# hand_main_v2.net
KiCad netlist of a schematic drawn in Altium Designer
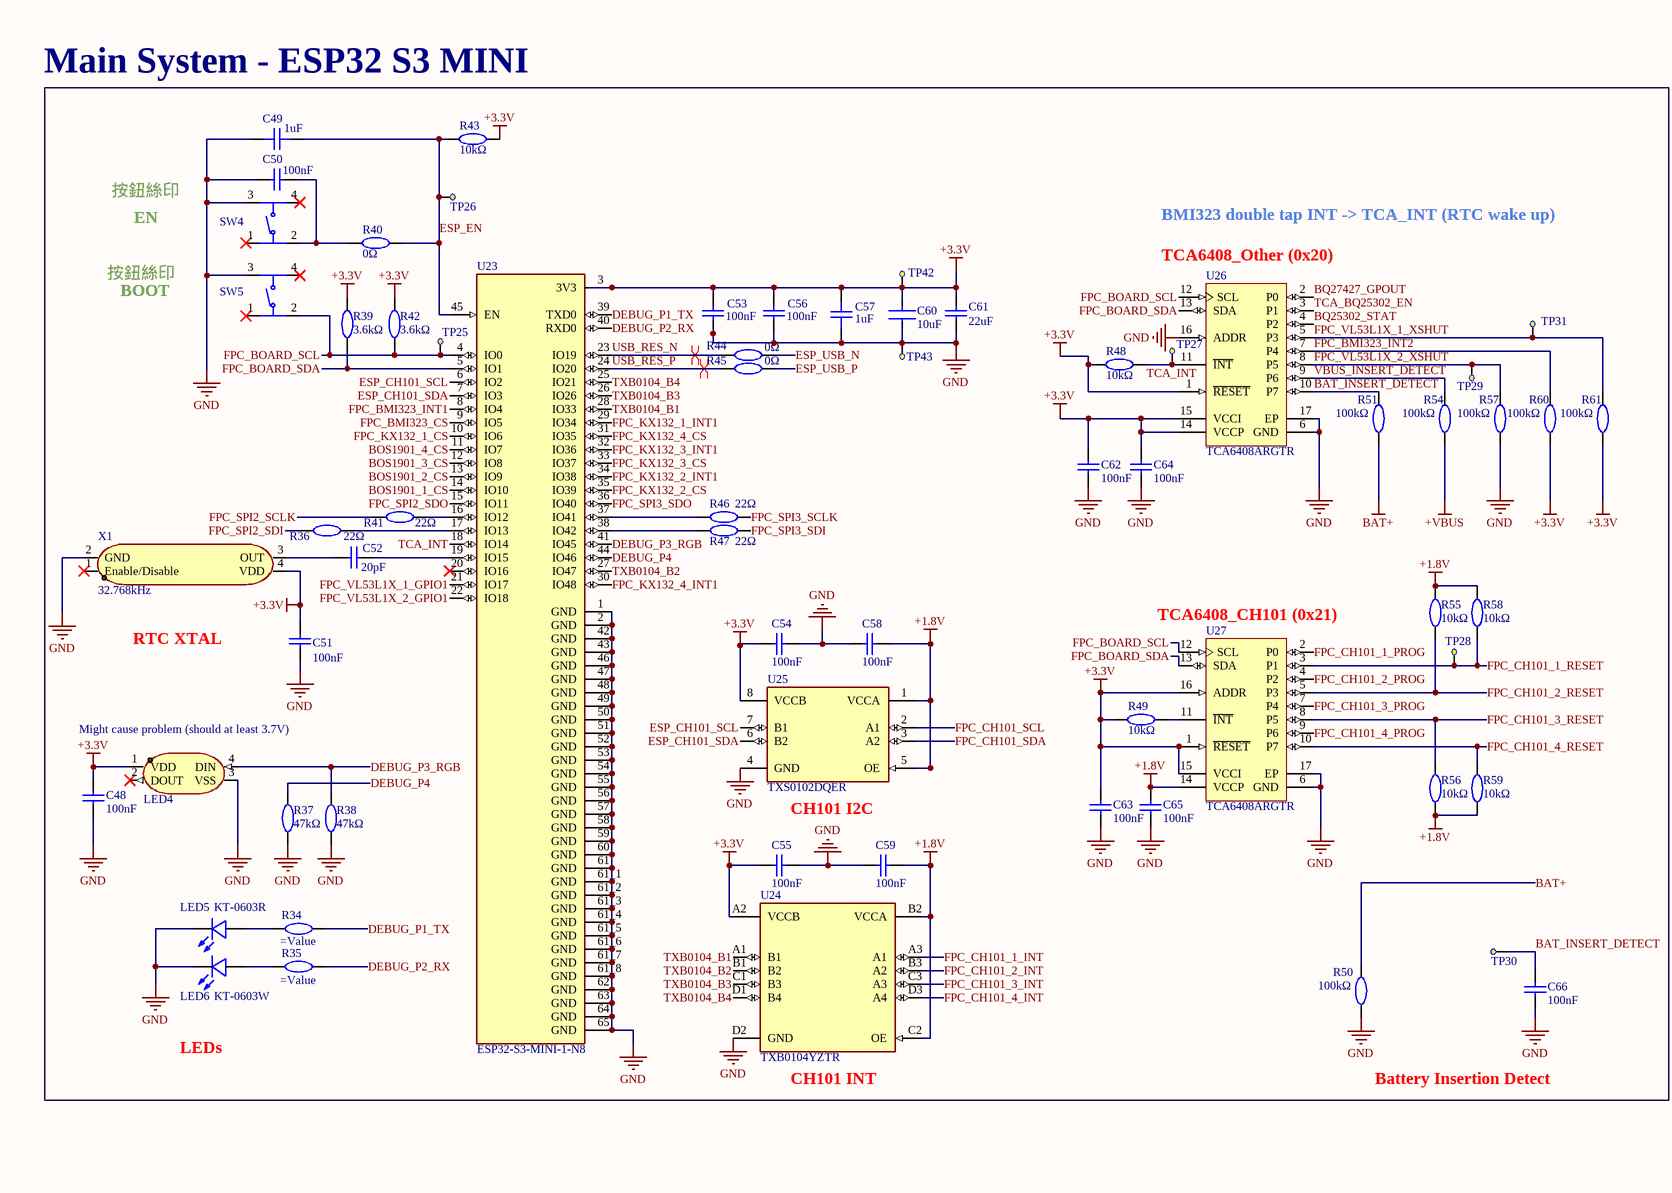
[diagram p0: hand_main_v2.SchDoc, left]
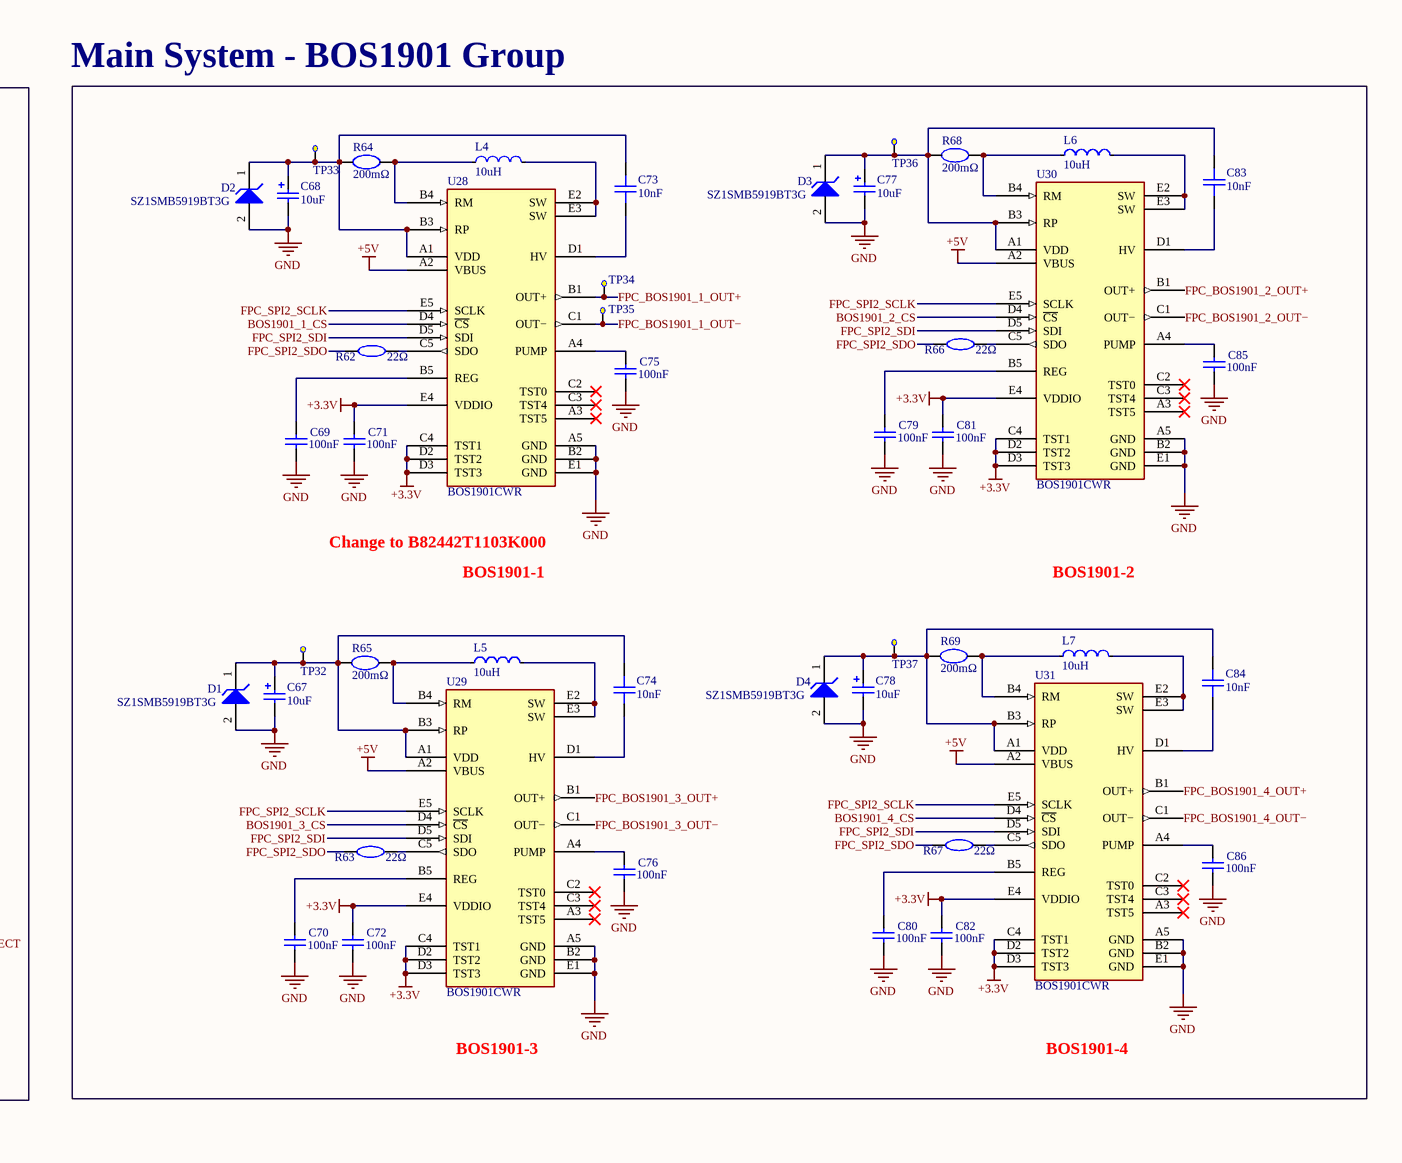
[diagram p1: hand_main_v2.SchDoc, middle]
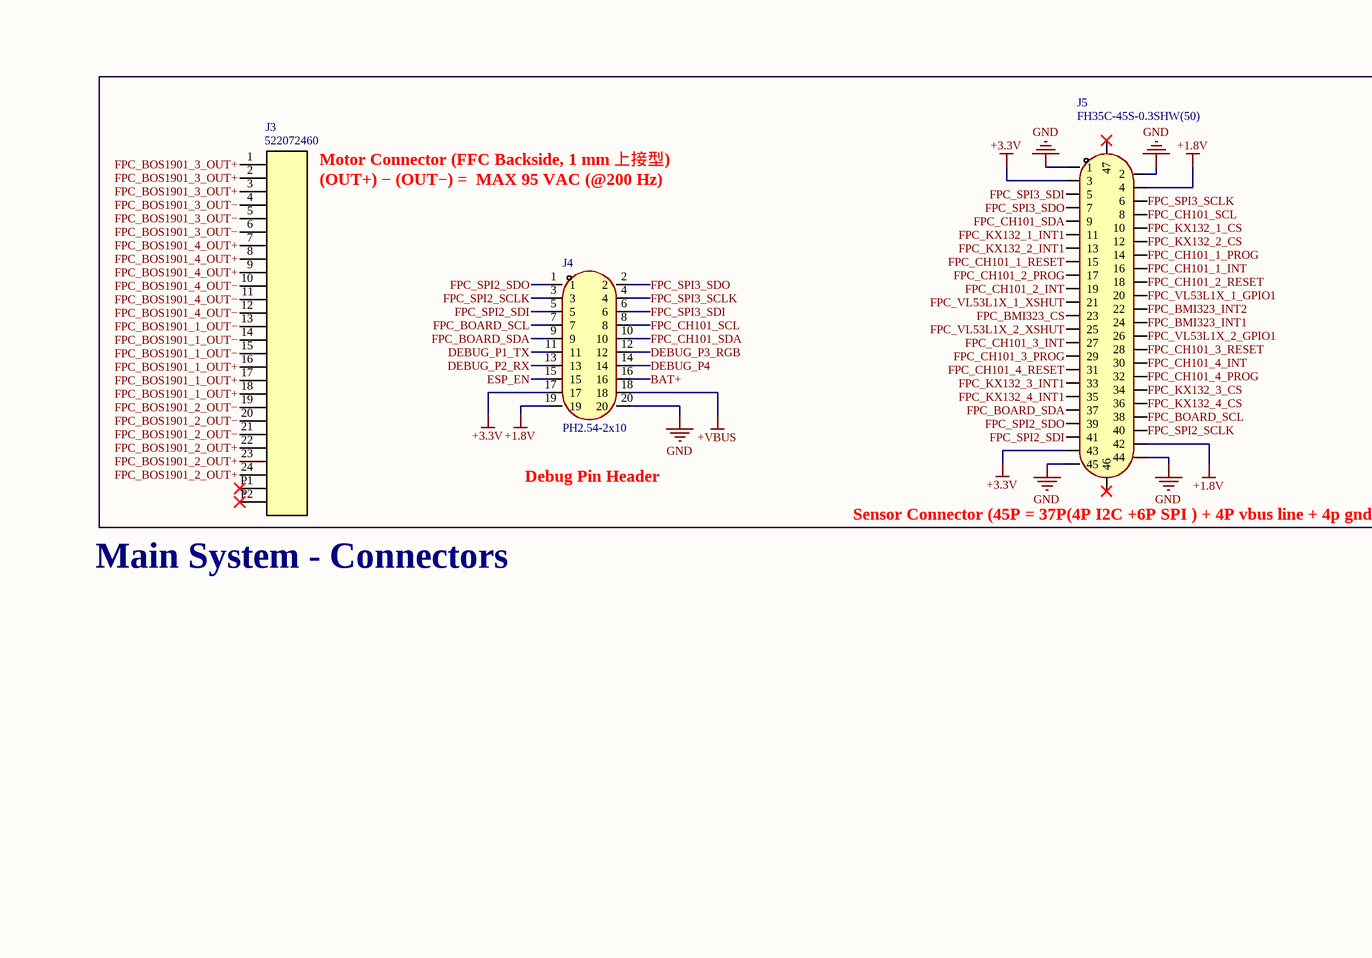
[diagram p2: hand_main_v2.SchDoc, right]

(export (version "E")
  (design (tool "Eeschema 10.0.6"))
  (components
    (comp (ref "C48")
      (value "100nF")
      (footprint "CAPC1050X55X23NL05T13")
      (description "Chip Capacitor, 100 nF, +/- 10%, 16 V, -55 to 125 degC, 0402 (1005 Metric), RoHS, Tape and Reel")
      (fields (field (name "MANUFACTURER") "Samsung Electro-Mechanics"))
      (libsource (lib "hand_ad_lib") (part "CL05B104KO5NNNC"))
    )
    (comp (ref "C49")
      (value "1uF")
      (footprint "C0402")
      (description "MLCC, 1 uF, 25 V, ± 10%, X5R, 0402 [1005 Metric]")
      (fields
        (field (name "MANUFACTURER") "SAMSUNG(三星)")
        (field (name "MANUFACTURER PART") "CL05A105KA5NQNC")
        (field (name "NAME") "1uF")
      )
      (libsource (lib "hand_ad_lib") (part "CL05A105KA5NQNC"))
    )
    (comp (ref "C50")
      (value "100nF")
      (footprint "CAPC1050X55X23NL05T13")
      (description "Chip Capacitor, 100 nF, +/- 10%, 16 V, -55 to 125 degC, 0402 (1005 Metric), RoHS, Tape and Reel")
      (fields (field (name "MANUFACTURER") "Samsung Electro-Mechanics"))
      (libsource (lib "hand_ad_lib") (part "CL05B104KO5NNNC"))
    )
    (comp (ref "C51")
      (value "100nF")
      (footprint "CAPC1050X55X23NL05T13")
      (description "Chip Capacitor, 100 nF, +/- 10%, 16 V, -55 to 125 degC, 0402 (1005 Metric), RoHS, Tape and Reel")
      (fields (field (name "MANUFACTURER") "Samsung Electro-Mechanics"))
      (libsource (lib "hand_ad_lib") (part "CL05B104KO5NNNC"))
    )
    (comp (ref "C52")
      (value "20pF")
      (footprint "C0603")
      (description "MLCC, 20pF, 50 V, ± 5%, C0G, 0603 [1608 Metric]")
      (fields
        (field (name "MANUFACTURER") "SAMSUNG(三星)")
        (field (name "MANUFACTURER PART") "CL10C200JB8NNNC")
        (field (name "NAME") "20pF")
      )
      (libsource (lib "hand_ad_lib") (part "CL10C200JB8NNNC"))
    )
    (comp (ref "C53")
      (value "100nF")
      (footprint "CAPC1050X55X23NL05T13")
      (description "Chip Capacitor, 100 nF, +/- 10%, 16 V, -55 to 125 degC, 0402 (1005 Metric), RoHS, Tape and Reel")
      (fields (field (name "MANUFACTURER") "Samsung Electro-Mechanics"))
      (libsource (lib "hand_ad_lib") (part "CL05B104KO5NNNC"))
    )
    (comp (ref "C54")
      (value "100nF")
      (footprint "CAPC1050X55X23NL05T13")
      (description "Chip Capacitor, 100 nF, +/- 10%, 16 V, -55 to 125 degC, 0402 (1005 Metric), RoHS, Tape and Reel")
      (fields (field (name "MANUFACTURER") "Samsung Electro-Mechanics"))
      (libsource (lib "hand_ad_lib") (part "CL05B104KO5NNNC"))
    )
    (comp (ref "C55")
      (value "100nF")
      (footprint "CAPC1050X55X23NL05T13")
      (description "Chip Capacitor, 100 nF, +/- 10%, 16 V, -55 to 125 degC, 0402 (1005 Metric), RoHS, Tape and Reel")
      (fields (field (name "MANUFACTURER") "Samsung Electro-Mechanics"))
      (libsource (lib "hand_ad_lib") (part "CL05B104KO5NNNC"))
    )
    (comp (ref "C56")
      (value "100nF")
      (footprint "CAPC1050X55X23NL05T13")
      (description "Chip Capacitor, 100 nF, +/- 10%, 16 V, -55 to 125 degC, 0402 (1005 Metric), RoHS, Tape and Reel")
      (fields (field (name "MANUFACTURER") "Samsung Electro-Mechanics"))
      (libsource (lib "hand_ad_lib") (part "CL05B104KO5NNNC"))
    )
    (comp (ref "C57")
      (value "1uF")
      (footprint "C0402")
      (description "MLCC, 1 uF, 25 V, ± 10%, X5R, 0402 [1005 Metric]")
      (fields
        (field (name "MANUFACTURER") "SAMSUNG(三星)")
        (field (name "MANUFACTURER PART") "CL05A105KA5NQNC")
        (field (name "NAME") "1uF")
      )
      (libsource (lib "hand_ad_lib") (part "CL05A105KA5NQNC"))
    )
    (comp (ref "C58")
      (value "100nF")
      (footprint "CAPC1050X55X23NL05T13")
      (description "Chip Capacitor, 100 nF, +/- 10%, 16 V, -55 to 125 degC, 0402 (1005 Metric), RoHS, Tape and Reel")
      (fields (field (name "MANUFACTURER") "Samsung Electro-Mechanics"))
      (libsource (lib "hand_ad_lib") (part "CL05B104KO5NNNC"))
    )
    (comp (ref "C59")
      (value "100nF")
      (footprint "CAPC1050X55X23NL05T13")
      (description "Chip Capacitor, 100 nF, +/- 10%, 16 V, -55 to 125 degC, 0402 (1005 Metric), RoHS, Tape and Reel")
      (fields (field (name "MANUFACTURER") "Samsung Electro-Mechanics"))
      (libsource (lib "hand_ad_lib") (part "CL05B104KO5NNNC"))
    )
    (comp (ref "C60")
      (value "10uF")
      (footprint "FP-CL10-IPC_A")
      (description "Cap Ceramic 10uF 25V X5R ±20% Pad SMD 0603 +85°C T/R")
      (fields (field (name "TOLERANCE") "20%"))
      (libsource (lib "hand_ad_lib") (part "CL10A106MA8NRNC"))
    )
    (comp (ref "C61")
      (value "22uF")
      (footprint "CAPC2013X140X45ML15T25")
      (description "Multi-layer Ceramic Capacitor, 22 uF, -55 to 85 degC, 2-Pin SMD (0805), RoHS, Tape and Reel")
      (fields (field (name "MANUFACTURER") "Samsung Electro-Mechanics") (field (name "TOLERANCE") "±20%"))
      (libsource (lib "hand_ad_lib") (part "CL21A226MAQNNNE"))
    )
    (comp (ref "C62")
      (value "100nF")
      (footprint "CAPC1050X55X23NL05T13")
      (description "Chip Capacitor, 100 nF, +/- 10%, 16 V, -55 to 125 degC, 0402 (1005 Metric), RoHS, Tape and Reel")
      (fields (field (name "MANUFACTURER") "Samsung Electro-Mechanics"))
      (libsource (lib "hand_ad_lib") (part "CL05B104KO5NNNC"))
    )
    (comp (ref "C63")
      (value "100nF")
      (footprint "CAPC1050X55X23NL05T13")
      (description "Chip Capacitor, 100 nF, +/- 10%, 16 V, -55 to 125 degC, 0402 (1005 Metric), RoHS, Tape and Reel")
      (fields (field (name "MANUFACTURER") "Samsung Electro-Mechanics"))
      (libsource (lib "hand_ad_lib") (part "CL05B104KO5NNNC"))
    )
    (comp (ref "C64")
      (value "100nF")
      (footprint "CAPC1050X55X23NL05T13")
      (description "Chip Capacitor, 100 nF, +/- 10%, 16 V, -55 to 125 degC, 0402 (1005 Metric), RoHS, Tape and Reel")
      (fields (field (name "MANUFACTURER") "Samsung Electro-Mechanics"))
      (libsource (lib "hand_ad_lib") (part "CL05B104KO5NNNC"))
    )
    (comp (ref "C65")
      (value "100nF")
      (footprint "CAPC1050X55X23NL05T13")
      (description "Chip Capacitor, 100 nF, +/- 10%, 16 V, -55 to 125 degC, 0402 (1005 Metric), RoHS, Tape and Reel")
      (fields (field (name "MANUFACTURER") "Samsung Electro-Mechanics"))
      (libsource (lib "hand_ad_lib") (part "CL05B104KO5NNNC"))
    )
    (comp (ref "C66")
      (value "100nF")
      (footprint "CAPC1050X55X23NL05T13")
      (description "Chip Capacitor, 100 nF, +/- 10%, 16 V, -55 to 125 degC, 0402 (1005 Metric), RoHS, Tape and Reel")
      (fields (field (name "MANUFACTURER") "Samsung Electro-Mechanics"))
      (libsource (lib "hand_ad_lib") (part "CL05B104KO5NNNC"))
    )
    (comp (ref "C67")
      (value "10uF")
      (footprint "CAP-SMD_L3.2-W1.6-RD-C7171")
      (fields
        (field (name "MANUFACTURER") "Kyocera AVX")
        (field (name "MANUFACTURER PART") "TAJA106K016RNJ")
        (field (name "TOLERANCE") "±10%")
        (field (name "NAME") "10uF")
      )
      (libsource (lib "hand_ad_lib") (part "TAJA106K016RNJ"))
    )
    (comp (ref "C68")
      (value "10uF")
      (footprint "CAP-SMD_L3.2-W1.6-RD-C7171")
      (fields
        (field (name "MANUFACTURER") "Kyocera AVX")
        (field (name "MANUFACTURER PART") "TAJA106K016RNJ")
        (field (name "TOLERANCE") "±10%")
        (field (name "NAME") "10uF")
      )
      (libsource (lib "hand_ad_lib") (part "TAJA106K016RNJ"))
    )
    (comp (ref "C69")
      (value "100nF")
      (footprint "CAPC1050X55X23NL05T13")
      (description "Chip Capacitor, 100 nF, +/- 10%, 16 V, -55 to 125 degC, 0402 (1005 Metric), RoHS, Tape and Reel")
      (fields (field (name "MANUFACTURER") "Samsung Electro-Mechanics"))
      (libsource (lib "hand_ad_lib") (part "CL05B104KO5NNNC"))
    )
    (comp (ref "C70")
      (value "100nF")
      (footprint "CAPC1050X55X23NL05T13")
      (description "Chip Capacitor, 100 nF, +/- 10%, 16 V, -55 to 125 degC, 0402 (1005 Metric), RoHS, Tape and Reel")
      (fields (field (name "MANUFACTURER") "Samsung Electro-Mechanics"))
      (libsource (lib "hand_ad_lib") (part "CL05B104KO5NNNC"))
    )
    (comp (ref "C71")
      (value "100nF")
      (footprint "CAPC1050X55X23NL05T13")
      (description "Chip Capacitor, 100 nF, +/- 10%, 16 V, -55 to 125 degC, 0402 (1005 Metric), RoHS, Tape and Reel")
      (fields (field (name "MANUFACTURER") "Samsung Electro-Mechanics"))
      (libsource (lib "hand_ad_lib") (part "CL05B104KO5NNNC"))
    )
    (comp (ref "C72")
      (value "100nF")
      (footprint "CAPC1050X55X23NL05T13")
      (description "Chip Capacitor, 100 nF, +/- 10%, 16 V, -55 to 125 degC, 0402 (1005 Metric), RoHS, Tape and Reel")
      (fields (field (name "MANUFACTURER") "Samsung Electro-Mechanics"))
      (libsource (lib "hand_ad_lib") (part "CL05B104KO5NNNC"))
    )
    (comp (ref "C73")
      (value "10nF")
      (footprint "C1206")
      (description "Cap Ceramic 0.01uF 250V C0G 5% SMD 1206 125°C Embossed T/R")
      (fields
        (field (name "MANUFACTURER") "muRata(村田)")
        (field (name "MANUFACTURER PART") "GCM31B5C2E103JX01L")
        (field (name "NAME") "10nF")
      )
      (libsource (lib "hand_ad_lib") (part "GCM31B5C2E103JX01L"))
    )
    (comp (ref "C74")
      (value "10nF")
      (footprint "C1206")
      (description "Cap Ceramic 0.01uF 250V C0G 5% SMD 1206 125°C Embossed T/R")
      (fields
        (field (name "MANUFACTURER") "muRata(村田)")
        (field (name "MANUFACTURER PART") "GCM31B5C2E103JX01L")
        (field (name "NAME") "10nF")
      )
      (libsource (lib "hand_ad_lib") (part "GCM31B5C2E103JX01L"))
    )
    (comp (ref "C75")
      (value "100nF")
      (footprint "CAPC1050X55X23NL05T13")
      (description "Chip Capacitor, 100 nF, +/- 10%, 16 V, -55 to 125 degC, 0402 (1005 Metric), RoHS, Tape and Reel")
      (fields (field (name "MANUFACTURER") "Samsung Electro-Mechanics"))
      (libsource (lib "hand_ad_lib") (part "CL05B104KO5NNNC"))
    )
    (comp (ref "C76")
      (value "100nF")
      (footprint "CAPC1050X55X23NL05T13")
      (description "Chip Capacitor, 100 nF, +/- 10%, 16 V, -55 to 125 degC, 0402 (1005 Metric), RoHS, Tape and Reel")
      (fields (field (name "MANUFACTURER") "Samsung Electro-Mechanics"))
      (libsource (lib "hand_ad_lib") (part "CL05B104KO5NNNC"))
    )
    (comp (ref "C77")
      (value "10uF")
      (footprint "CAP-SMD_L3.2-W1.6-RD-C7171")
      (fields
        (field (name "MANUFACTURER") "Kyocera AVX")
        (field (name "MANUFACTURER PART") "TAJA106K016RNJ")
        (field (name "TOLERANCE") "±10%")
        (field (name "NAME") "10uF")
      )
      (libsource (lib "hand_ad_lib") (part "TAJA106K016RNJ"))
    )
    (comp (ref "C78")
      (value "10uF")
      (footprint "CAP-SMD_L3.2-W1.6-RD-C7171")
      (fields
        (field (name "MANUFACTURER") "Kyocera AVX")
        (field (name "MANUFACTURER PART") "TAJA106K016RNJ")
        (field (name "TOLERANCE") "±10%")
        (field (name "NAME") "10uF")
      )
      (libsource (lib "hand_ad_lib") (part "TAJA106K016RNJ"))
    )
    (comp (ref "C79")
      (value "100nF")
      (footprint "CAPC1050X55X23NL05T13")
      (description "Chip Capacitor, 100 nF, +/- 10%, 16 V, -55 to 125 degC, 0402 (1005 Metric), RoHS, Tape and Reel")
      (fields (field (name "MANUFACTURER") "Samsung Electro-Mechanics"))
      (libsource (lib "hand_ad_lib") (part "CL05B104KO5NNNC"))
    )
    (comp (ref "C80")
      (value "100nF")
      (footprint "CAPC1050X55X23NL05T13")
      (description "Chip Capacitor, 100 nF, +/- 10%, 16 V, -55 to 125 degC, 0402 (1005 Metric), RoHS, Tape and Reel")
      (fields (field (name "MANUFACTURER") "Samsung Electro-Mechanics"))
      (libsource (lib "hand_ad_lib") (part "CL05B104KO5NNNC"))
    )
    (comp (ref "C81")
      (value "100nF")
      (footprint "CAPC1050X55X23NL05T13")
      (description "Chip Capacitor, 100 nF, +/- 10%, 16 V, -55 to 125 degC, 0402 (1005 Metric), RoHS, Tape and Reel")
      (fields (field (name "MANUFACTURER") "Samsung Electro-Mechanics"))
      (libsource (lib "hand_ad_lib") (part "CL05B104KO5NNNC"))
    )
    (comp (ref "C82")
      (value "100nF")
      (footprint "CAPC1050X55X23NL05T13")
      (description "Chip Capacitor, 100 nF, +/- 10%, 16 V, -55 to 125 degC, 0402 (1005 Metric), RoHS, Tape and Reel")
      (fields (field (name "MANUFACTURER") "Samsung Electro-Mechanics"))
      (libsource (lib "hand_ad_lib") (part "CL05B104KO5NNNC"))
    )
    (comp (ref "C83")
      (value "10nF")
      (footprint "C1206")
      (description "Cap Ceramic 0.01uF 250V C0G 5% SMD 1206 125°C Embossed T/R")
      (fields
        (field (name "MANUFACTURER") "muRata(村田)")
        (field (name "MANUFACTURER PART") "GCM31B5C2E103JX01L")
        (field (name "NAME") "10nF")
      )
      (libsource (lib "hand_ad_lib") (part "GCM31B5C2E103JX01L"))
    )
    (comp (ref "C84")
      (value "10nF")
      (footprint "C1206")
      (description "Cap Ceramic 0.01uF 250V C0G 5% SMD 1206 125°C Embossed T/R")
      (fields
        (field (name "MANUFACTURER") "muRata(村田)")
        (field (name "MANUFACTURER PART") "GCM31B5C2E103JX01L")
        (field (name "NAME") "10nF")
      )
      (libsource (lib "hand_ad_lib") (part "GCM31B5C2E103JX01L"))
    )
    (comp (ref "C85")
      (value "100nF")
      (footprint "CAPC1050X55X23NL05T13")
      (description "Chip Capacitor, 100 nF, +/- 10%, 16 V, -55 to 125 degC, 0402 (1005 Metric), RoHS, Tape and Reel")
      (fields (field (name "MANUFACTURER") "Samsung Electro-Mechanics"))
      (libsource (lib "hand_ad_lib") (part "CL05B104KO5NNNC"))
    )
    (comp (ref "C86")
      (value "100nF")
      (footprint "CAPC1050X55X23NL05T13")
      (description "Chip Capacitor, 100 nF, +/- 10%, 16 V, -55 to 125 degC, 0402 (1005 Metric), RoHS, Tape and Reel")
      (fields (field (name "MANUFACTURER") "Samsung Electro-Mechanics"))
      (libsource (lib "hand_ad_lib") (part "CL05B104KO5NNNC"))
    )
    (comp (ref "D1")
      (value "SZ1SMB5919BT3G")
      (footprint "ONSC-SMB-2-403A-03_H_V")
      (description "3 W Zener Voltage Regulator, 2-Pin SMB, Pb-Free, Tape and Reel")
      (fields (field (name "MANUFACTURER") "On Semiconductor"))
      (libsource (lib "hand_ad_lib") (part "SZ1SMB5919BT3G"))
    )
    (comp (ref "D2")
      (value "SZ1SMB5919BT3G")
      (footprint "ONSC-SMB-2-403A-03_H_V")
      (description "3 W Zener Voltage Regulator, 2-Pin SMB, Pb-Free, Tape and Reel")
      (fields (field (name "MANUFACTURER") "On Semiconductor"))
      (libsource (lib "hand_ad_lib") (part "SZ1SMB5919BT3G"))
    )
    (comp (ref "D3")
      (value "SZ1SMB5919BT3G")
      (footprint "ONSC-SMB-2-403A-03_H_V")
      (description "3 W Zener Voltage Regulator, 2-Pin SMB, Pb-Free, Tape and Reel")
      (fields (field (name "MANUFACTURER") "On Semiconductor"))
      (libsource (lib "hand_ad_lib") (part "SZ1SMB5919BT3G"))
    )
    (comp (ref "D4")
      (value "SZ1SMB5919BT3G")
      (footprint "ONSC-SMB-2-403A-03_H_V")
      (description "3 W Zener Voltage Regulator, 2-Pin SMB, Pb-Free, Tape and Reel")
      (fields (field (name "MANUFACTURER") "On Semiconductor"))
      (libsource (lib "hand_ad_lib") (part "SZ1SMB5919BT3G"))
    )
    (comp (ref "J3")
      (value "522072460")
      (footprint "CON_522072460_MOL")
      (description "FFC 1mm 24P")
      (libsource (lib "hand_ad_lib") (part "522072460"))
    )
    (comp (ref "J4")
      (value "PH2.54-2x10")
      (footprint "HDR-TH_20P-P2.54-V-M-R2-C10-S2.54")
      (description "Pin Header 2.54mm, 2x10")
      (fields (field (name "MANUFACTURER") "ZHOURI(洲日)") (field (name "NAME") "PH2.54-2x10"))
      (libsource (lib "hand_ad_lib") (part "PH2.54-2x10"))
    )
    (comp (ref "J5")
      (value "FH35C-45S-0.3SHW(50)")
      (footprint "FPC-SMD_FH35C-45S-0.3SHW-50")
      (description "FPC Connector, 45P, 0.3mm, Right Angle, Double Side Connection")
      (fields (field (name "MANUFACTURER") "HRS(广濑)") (field (name "NAME") "FH35C-45S-0.3SHW(50)"))
      (libsource (lib "hand_ad_lib") (part "FH35C-45S-0.3SHW(50)"))
    )
    (comp (ref "L4")
      (value "10uH")
      (footprint "IND-SMD_L7.8-W7.0-A")
      (description "Ind Power Unshielded Wirewound 10uH 10% 2.52MHz 2.3A Carrier T/R")
      (fields
        (field (name "MANUFACTURER") "Sumida(胜美达)")
        (field (name "MANUFACTURER PART") "CD75T125NP-100KC")
        (field (name "NAME") "10uH")
      )
      (libsource (lib "hand_ad_lib") (part "CD75T125NP-100KC"))
    )
    (comp (ref "L5")
      (value "10uH")
      (footprint "IND-SMD_L7.8-W7.0-A")
      (description "Ind Power Unshielded Wirewound 10uH 10% 2.52MHz 2.3A Carrier T/R")
      (fields
        (field (name "MANUFACTURER") "Sumida(胜美达)")
        (field (name "MANUFACTURER PART") "CD75T125NP-100KC")
        (field (name "NAME") "10uH")
      )
      (libsource (lib "hand_ad_lib") (part "CD75T125NP-100KC"))
    )
    (comp (ref "L6")
      (value "10uH")
      (footprint "IND-SMD_L7.8-W7.0-A")
      (description "Ind Power Unshielded Wirewound 10uH 10% 2.52MHz 2.3A Carrier T/R")
      (fields
        (field (name "MANUFACTURER") "Sumida(胜美达)")
        (field (name "MANUFACTURER PART") "CD75T125NP-100KC")
        (field (name "NAME") "10uH")
      )
      (libsource (lib "hand_ad_lib") (part "CD75T125NP-100KC"))
    )
    (comp (ref "L7")
      (value "10uH")
      (footprint "IND-SMD_L7.8-W7.0-A")
      (description "Ind Power Unshielded Wirewound 10uH 10% 2.52MHz 2.3A Carrier T/R")
      (fields
        (field (name "MANUFACTURER") "Sumida(胜美达)")
        (field (name "MANUFACTURER PART") "CD75T125NP-100KC")
        (field (name "NAME") "10uH")
      )
      (libsource (lib "hand_ad_lib") (part "CD75T125NP-100KC"))
    )
    (comp (ref "LED4")
      (value "WS2812B-MINI-V3/W")
      (footprint "LED-SMD_4P-L3.5-W3.5-TL_WS2812B")
      (fields (field (name "MANUFACTURER") "worldsemi"))
      (libsource (lib "hand_ad_lib") (part "WS2812B-MINI-V3/W"))
    )
    (comp (ref "LED5")
      (value "KT-0603R")
      (footprint "LED0603-RD")
      (description "LED, Red 0603")
      (fields (field (name "MANUFACTURER") "KENTO") (field (name "NAME") "KT-0603R"))
      (libsource (lib "hand_ad_lib") (part "KT-0603R"))
    )
    (comp (ref "LED6")
      (value "KT-0603W")
      (footprint "LED0603-R-RD_WHITE")
      (description "LED, White 0603")
      (fields (field (name "MANUFACTURER") "KENTO") (field (name "NAME") "KT-0603W"))
      (libsource (lib "hand_ad_lib") (part "KT-0603W"))
    )
    (comp (ref "R34")
      (value "~")
      (footprint "R0402")
      (description "Resistor, Res Thick Film 0402 1K Ohm 1% 0.063W(1/16W) ±100ppm/°C Pad SMD T/R")
      (fields
        (field (name "MANUFACTURER") "UNI-ROYAL(厚声)")
        (field (name "MANUFACTURER PART") "0402WGF1001TCE")
      )
      (libsource (lib "hand_ad_lib") (part "0402WGF1001TCE"))
    )
    (comp (ref "R35")
      (value "~")
      (footprint "R0402")
      (description "Resistor, Res Thick Film 0402 1K Ohm 1% 0.063W(1/16W) ±100ppm/°C Pad SMD T/R")
      (fields
        (field (name "MANUFACTURER") "UNI-ROYAL(厚声)")
        (field (name "MANUFACTURER PART") "0402WGF1001TCE")
      )
      (libsource (lib "hand_ad_lib") (part "0402WGF1001TCE"))
    )
    (comp (ref "R36")
      (value "22Ω")
      (footprint "R0402")
      (description "Resistor, Res Thick Film 0402 22 Ohm 1% 0.063W(1/16W) ±200ppm/°C Pad SMD T/R")
      (fields
        (field (name "MANUFACTURER") "UNI-ROYAL(厚声)")
        (field (name "MANUFACTURER PART") "0402WGF220JTCE")
        (field (name "NAME") "22Ω")
      )
      (libsource (lib "hand_ad_lib") (part "0402WGF220JTCE"))
    )
    (comp (ref "R37")
      (value "47kΩ")
      (footprint "R0402")
      (description "Resistor, Res Thick Film 0402 47K Ohm 1% 0.063W(1/16W) ±100ppm/°C Pad SMD T/R")
      (fields
        (field (name "MANUFACTURER") "UNI-ROYAL(厚声)")
        (field (name "MANUFACTURER PART") "0402WGF4702TCE")
        (field (name "NAME") "47kΩ")
      )
      (libsource (lib "hand_ad_lib") (part "0402WGF4702TCE"))
    )
    (comp (ref "R38")
      (value "47kΩ")
      (footprint "R0402")
      (description "Resistor, Res Thick Film 0402 47K Ohm 1% 0.063W(1/16W) ±100ppm/°C Pad SMD T/R")
      (fields
        (field (name "MANUFACTURER") "UNI-ROYAL(厚声)")
        (field (name "MANUFACTURER PART") "0402WGF4702TCE")
        (field (name "NAME") "47kΩ")
      )
      (libsource (lib "hand_ad_lib") (part "0402WGF4702TCE"))
    )
    (comp (ref "R39")
      (value "3.6kΩ")
      (footprint "R0603")
      (description "Resistor, Res Thick Film 0603 3.6K Ohm 1% 0.1W ±100ppm/°C Pad SMD T/R")
      (fields
        (field (name "MANUFACTURER") "UNI-ROYAL(厚声)")
        (field (name "MANUFACTURER PART") "0603WAF3601T5E")
        (field (name "NAME") "3.6kΩ")
      )
      (libsource (lib "hand_ad_lib") (part "0603WAF3601T5E"))
    )
    (comp (ref "R40")
      (value "0Ω")
      (footprint "R0402")
      (description "Resistor, Res Thick Film 0402 0 Ohm 1% 0.063W(1/16W) ±800ppm/°C Pad SMD T/R")
      (fields
        (field (name "MANUFACTURER") "UNI-ROYAL(厚声)")
        (field (name "MANUFACTURER PART") "0402WGF0000TCE")
        (field (name "NAME") "0Ω")
      )
      (libsource (lib "hand_ad_lib") (part "0402WGF0000TCE"))
    )
    (comp (ref "R41")
      (value "22Ω")
      (footprint "R0402")
      (description "Resistor, Res Thick Film 0402 22 Ohm 1% 0.063W(1/16W) ±200ppm/°C Pad SMD T/R")
      (fields
        (field (name "MANUFACTURER") "UNI-ROYAL(厚声)")
        (field (name "MANUFACTURER PART") "0402WGF220JTCE")
        (field (name "NAME") "22Ω")
      )
      (libsource (lib "hand_ad_lib") (part "0402WGF220JTCE"))
    )
    (comp (ref "R42")
      (value "3.6kΩ")
      (footprint "R0603")
      (description "Resistor, Res Thick Film 0603 3.6K Ohm 1% 0.1W ±100ppm/°C Pad SMD T/R")
      (fields
        (field (name "MANUFACTURER") "UNI-ROYAL(厚声)")
        (field (name "MANUFACTURER PART") "0603WAF3601T5E")
        (field (name "NAME") "3.6kΩ")
      )
      (libsource (lib "hand_ad_lib") (part "0603WAF3601T5E"))
    )
    (comp (ref "R43")
      (value "10kΩ")
      (footprint "R0402")
      (description "Resistor, Res Thick Film 0402 10K Ohm 1% 0.063W(1/16W) ±100ppm/°C Pad SMD T/R")
      (fields
        (field (name "MANUFACTURER") "UNI-ROYAL(厚声)")
        (field (name "MANUFACTURER PART") "0402WGF1002TCE")
        (field (name "NAME") "10kΩ")
      )
      (libsource (lib "hand_ad_lib") (part "0402WGF1002TCE"))
    )
    (comp (ref "R44")
      (value "0Ω")
      (footprint "R0402")
      (description "Resistor, Res Thick Film 0402 0 Ohm 1% 0.063W(1/16W) ±800ppm/°C Pad SMD T/R")
      (fields
        (field (name "MANUFACTURER") "UNI-ROYAL(厚声)")
        (field (name "MANUFACTURER PART") "0402WGF0000TCE")
        (field (name "NAME") "0Ω")
      )
      (libsource (lib "hand_ad_lib") (part "0402WGF0000TCE"))
    )
    (comp (ref "R45")
      (value "0Ω")
      (footprint "R0402")
      (description "Resistor, Res Thick Film 0402 0 Ohm 1% 0.063W(1/16W) ±800ppm/°C Pad SMD T/R")
      (fields
        (field (name "MANUFACTURER") "UNI-ROYAL(厚声)")
        (field (name "MANUFACTURER PART") "0402WGF0000TCE")
        (field (name "NAME") "0Ω")
      )
      (libsource (lib "hand_ad_lib") (part "0402WGF0000TCE"))
    )
    (comp (ref "R46")
      (value "22Ω")
      (footprint "R0402")
      (description "Resistor, Res Thick Film 0402 22 Ohm 1% 0.063W(1/16W) ±200ppm/°C Pad SMD T/R")
      (fields
        (field (name "MANUFACTURER") "UNI-ROYAL(厚声)")
        (field (name "MANUFACTURER PART") "0402WGF220JTCE")
        (field (name "NAME") "22Ω")
      )
      (libsource (lib "hand_ad_lib") (part "0402WGF220JTCE"))
    )
    (comp (ref "R47")
      (value "22Ω")
      (footprint "R0402")
      (description "Resistor, Res Thick Film 0402 22 Ohm 1% 0.063W(1/16W) ±200ppm/°C Pad SMD T/R")
      (fields
        (field (name "MANUFACTURER") "UNI-ROYAL(厚声)")
        (field (name "MANUFACTURER PART") "0402WGF220JTCE")
        (field (name "NAME") "22Ω")
      )
      (libsource (lib "hand_ad_lib") (part "0402WGF220JTCE"))
    )
    (comp (ref "R48")
      (value "10kΩ")
      (footprint "R0402")
      (description "Resistor, Res Thick Film 0402 10K Ohm 1% 0.063W(1/16W) ±100ppm/°C Pad SMD T/R")
      (fields
        (field (name "MANUFACTURER") "UNI-ROYAL(厚声)")
        (field (name "MANUFACTURER PART") "0402WGF1002TCE")
        (field (name "NAME") "10kΩ")
      )
      (libsource (lib "hand_ad_lib") (part "0402WGF1002TCE"))
    )
    (comp (ref "R49")
      (value "10kΩ")
      (footprint "R0402")
      (description "Resistor, Res Thick Film 0402 10K Ohm 1% 0.063W(1/16W) ±100ppm/°C Pad SMD T/R")
      (fields
        (field (name "MANUFACTURER") "UNI-ROYAL(厚声)")
        (field (name "MANUFACTURER PART") "0402WGF1002TCE")
        (field (name "NAME") "10kΩ")
      )
      (libsource (lib "hand_ad_lib") (part "0402WGF1002TCE"))
    )
    (comp (ref "R50")
      (value "100kΩ")
      (footprint "R0402")
      (description "Resistor, Res Thick Film 0402 100K Ohm 1% 0.063W(1/16W) ±100ppm/°C Pad SMD T/R")
      (fields
        (field (name "MANUFACTURER") "UNI-ROYAL(厚声)")
        (field (name "MANUFACTURER PART") "0402WGF1003TCE")
        (field (name "NAME") "100kΩ")
      )
      (libsource (lib "hand_ad_lib") (part "0402WGF1003TCE"))
    )
    (comp (ref "R51")
      (value "100kΩ")
      (footprint "R0402")
      (description "Resistor, Res Thick Film 0402 100K Ohm 1% 0.063W(1/16W) ±100ppm/°C Pad SMD T/R")
      (fields
        (field (name "MANUFACTURER") "UNI-ROYAL(厚声)")
        (field (name "MANUFACTURER PART") "0402WGF1003TCE")
        (field (name "NAME") "100kΩ")
      )
      (libsource (lib "hand_ad_lib") (part "0402WGF1003TCE"))
    )
    (comp (ref "R54")
      (value "100kΩ")
      (footprint "R0402")
      (description "Resistor, Res Thick Film 0402 100K Ohm 1% 0.063W(1/16W) ±100ppm/°C Pad SMD T/R")
      (fields
        (field (name "MANUFACTURER") "UNI-ROYAL(厚声)")
        (field (name "MANUFACTURER PART") "0402WGF1003TCE")
        (field (name "NAME") "100kΩ")
      )
      (libsource (lib "hand_ad_lib") (part "0402WGF1003TCE"))
    )
    (comp (ref "R55")
      (value "10kΩ")
      (footprint "R0402")
      (description "Resistor, Res Thick Film 0402 10K Ohm 1% 0.063W(1/16W) ±100ppm/°C Pad SMD T/R")
      (fields
        (field (name "MANUFACTURER") "UNI-ROYAL(厚声)")
        (field (name "MANUFACTURER PART") "0402WGF1002TCE")
        (field (name "NAME") "10kΩ")
      )
      (libsource (lib "hand_ad_lib") (part "0402WGF1002TCE"))
    )
    (comp (ref "R56")
      (value "10kΩ")
      (footprint "R0402")
      (description "Resistor, Res Thick Film 0402 10K Ohm 1% 0.063W(1/16W) ±100ppm/°C Pad SMD T/R")
      (fields
        (field (name "MANUFACTURER") "UNI-ROYAL(厚声)")
        (field (name "MANUFACTURER PART") "0402WGF1002TCE")
        (field (name "NAME") "10kΩ")
      )
      (libsource (lib "hand_ad_lib") (part "0402WGF1002TCE"))
    )
    (comp (ref "R57")
      (value "100kΩ")
      (footprint "R0402")
      (description "Resistor, Res Thick Film 0402 100K Ohm 1% 0.063W(1/16W) ±100ppm/°C Pad SMD T/R")
      (fields
        (field (name "MANUFACTURER") "UNI-ROYAL(厚声)")
        (field (name "MANUFACTURER PART") "0402WGF1003TCE")
        (field (name "NAME") "100kΩ")
      )
      (libsource (lib "hand_ad_lib") (part "0402WGF1003TCE"))
    )
    (comp (ref "R58")
      (value "10kΩ")
      (footprint "R0402")
      (description "Resistor, Res Thick Film 0402 10K Ohm 1% 0.063W(1/16W) ±100ppm/°C Pad SMD T/R")
      (fields
        (field (name "MANUFACTURER") "UNI-ROYAL(厚声)")
        (field (name "MANUFACTURER PART") "0402WGF1002TCE")
        (field (name "NAME") "10kΩ")
      )
      (libsource (lib "hand_ad_lib") (part "0402WGF1002TCE"))
    )
    (comp (ref "R59")
      (value "10kΩ")
      (footprint "R0402")
      (description "Resistor, Res Thick Film 0402 10K Ohm 1% 0.063W(1/16W) ±100ppm/°C Pad SMD T/R")
      (fields
        (field (name "MANUFACTURER") "UNI-ROYAL(厚声)")
        (field (name "MANUFACTURER PART") "0402WGF1002TCE")
        (field (name "NAME") "10kΩ")
      )
      (libsource (lib "hand_ad_lib") (part "0402WGF1002TCE"))
    )
    (comp (ref "R60")
      (value "100kΩ")
      (footprint "R0402")
      (description "Resistor, Res Thick Film 0402 100K Ohm 1% 0.063W(1/16W) ±100ppm/°C Pad SMD T/R")
      (fields
        (field (name "MANUFACTURER") "UNI-ROYAL(厚声)")
        (field (name "MANUFACTURER PART") "0402WGF1003TCE")
        (field (name "NAME") "100kΩ")
      )
      (libsource (lib "hand_ad_lib") (part "0402WGF1003TCE"))
    )
    (comp (ref "R61")
      (value "100kΩ")
      (footprint "R0402")
      (description "Resistor, Res Thick Film 0402 100K Ohm 1% 0.063W(1/16W) ±100ppm/°C Pad SMD T/R")
      (fields
        (field (name "MANUFACTURER") "UNI-ROYAL(厚声)")
        (field (name "MANUFACTURER PART") "0402WGF1003TCE")
        (field (name "NAME") "100kΩ")
      )
      (libsource (lib "hand_ad_lib") (part "0402WGF1003TCE"))
    )
    (comp (ref "R62")
      (value "22Ω")
      (footprint "R0402")
      (description "Resistor, Res Thick Film 0402 22 Ohm 1% 0.063W(1/16W) ±200ppm/°C Pad SMD T/R")
      (fields
        (field (name "MANUFACTURER") "UNI-ROYAL(厚声)")
        (field (name "MANUFACTURER PART") "0402WGF220JTCE")
        (field (name "NAME") "22Ω")
      )
      (libsource (lib "hand_ad_lib") (part "0402WGF220JTCE"))
    )
    (comp (ref "R63")
      (value "22Ω")
      (footprint "R0402")
      (description "Resistor, Res Thick Film 0402 22 Ohm 1% 0.063W(1/16W) ±200ppm/°C Pad SMD T/R")
      (fields
        (field (name "MANUFACTURER") "UNI-ROYAL(厚声)")
        (field (name "MANUFACTURER PART") "0402WGF220JTCE")
        (field (name "NAME") "22Ω")
      )
      (libsource (lib "hand_ad_lib") (part "0402WGF220JTCE"))
    )
    (comp (ref "R64")
      (value "200mΩ")
      (footprint "R1206")
      (fields
        (field (name "MANUFACTURER") "Milliohm(毫欧)")
        (field (name "MANUFACTURER PART") "HoYH1206-1W-200mR-1%")
        (field (name "TOLERANCE") "±1%")
        (field (name "NAME") "200mΩ")
      )
      (libsource (lib "hand_ad_lib") (part "HoYH1206-1W-200mR-1%"))
    )
    (comp (ref "R65")
      (value "200mΩ")
      (footprint "R1206")
      (fields
        (field (name "MANUFACTURER") "Milliohm(毫欧)")
        (field (name "MANUFACTURER PART") "HoYH1206-1W-200mR-1%")
        (field (name "TOLERANCE") "±1%")
        (field (name "NAME") "200mΩ")
      )
      (libsource (lib "hand_ad_lib") (part "HoYH1206-1W-200mR-1%"))
    )
    (comp (ref "R66")
      (value "22Ω")
      (footprint "R0402")
      (description "Resistor, Res Thick Film 0402 22 Ohm 1% 0.063W(1/16W) ±200ppm/°C Pad SMD T/R")
      (fields
        (field (name "MANUFACTURER") "UNI-ROYAL(厚声)")
        (field (name "MANUFACTURER PART") "0402WGF220JTCE")
        (field (name "NAME") "22Ω")
      )
      (libsource (lib "hand_ad_lib") (part "0402WGF220JTCE"))
    )
    (comp (ref "R67")
      (value "22Ω")
      (footprint "R0402")
      (description "Resistor, Res Thick Film 0402 22 Ohm 1% 0.063W(1/16W) ±200ppm/°C Pad SMD T/R")
      (fields
        (field (name "MANUFACTURER") "UNI-ROYAL(厚声)")
        (field (name "MANUFACTURER PART") "0402WGF220JTCE")
        (field (name "NAME") "22Ω")
      )
      (libsource (lib "hand_ad_lib") (part "0402WGF220JTCE"))
    )
    (comp (ref "R68")
      (value "200mΩ")
      (footprint "R1206")
      (fields
        (field (name "MANUFACTURER") "Milliohm(毫欧)")
        (field (name "MANUFACTURER PART") "HoYH1206-1W-200mR-1%")
        (field (name "TOLERANCE") "±1%")
        (field (name "NAME") "200mΩ")
      )
      (libsource (lib "hand_ad_lib") (part "HoYH1206-1W-200mR-1%"))
    )
    (comp (ref "R69")
      (value "200mΩ")
      (footprint "R1206")
      (fields
        (field (name "MANUFACTURER") "Milliohm(毫欧)")
        (field (name "MANUFACTURER PART") "HoYH1206-1W-200mR-1%")
        (field (name "TOLERANCE") "±1%")
        (field (name "NAME") "200mΩ")
      )
      (libsource (lib "hand_ad_lib") (part "HoYH1206-1W-200mR-1%"))
    )
    (comp (ref "SW4")
      (value "TS-1187A-B-A-B")
      (footprint "SW-SMD_4P-L5.1-W5.1-P3.70-LS6.5-TL-2")
      (description "Touch Button")
      (fields (field (name "MANUFACTURER") "XKB Connectivity(中国星坤)"))
      (libsource (lib "hand_ad_lib") (part "TS-1187A-B-A-B"))
    )
    (comp (ref "SW5")
      (value "TS-1187A-B-A-B")
      (footprint "SW-SMD_4P-L5.1-W5.1-P3.70-LS6.5-TL-2")
      (description "Touch Button, Boot")
      (fields (field (name "MANUFACTURER") "XKB Connectivity(中国星坤)"))
      (libsource (lib "hand_ad_lib") (part "TS-1187A-B-A-B"))
    )
    (comp (ref "TP25")
      (value "Test point")
      (footprint "Test_Point")
      (libsource (lib "hand_ad_lib") (part "Test_Point"))
    )
    (comp (ref "TP26")
      (value "Test point")
      (footprint "Test_Point")
      (libsource (lib "hand_ad_lib") (part "Test_Point"))
    )
    (comp (ref "TP27")
      (value "Test point")
      (footprint "Test_Point")
      (libsource (lib "hand_ad_lib") (part "Test_Point"))
    )
    (comp (ref "TP28")
      (value "Test point")
      (footprint "Test_Point")
      (libsource (lib "hand_ad_lib") (part "Test_Point"))
    )
    (comp (ref "TP29")
      (value "Test point")
      (footprint "Test_Point")
      (libsource (lib "hand_ad_lib") (part "Test_Point"))
    )
    (comp (ref "TP30")
      (value "Test point")
      (footprint "Test_Point")
      (libsource (lib "hand_ad_lib") (part "Test_Point"))
    )
    (comp (ref "TP31")
      (value "Test point")
      (footprint "Test_Point")
      (libsource (lib "hand_ad_lib") (part "Test_Point"))
    )
    (comp (ref "TP32")
      (value "Test point")
      (footprint "Test_Point")
      (libsource (lib "hand_ad_lib") (part "Test_Point"))
    )
    (comp (ref "TP33")
      (value "Test point")
      (footprint "Test_Point")
      (libsource (lib "hand_ad_lib") (part "Test_Point"))
    )
    (comp (ref "TP34")
      (value "Test point")
      (footprint "Test_Point")
      (libsource (lib "hand_ad_lib") (part "Test_Point"))
    )
    (comp (ref "TP35")
      (value "Test point")
      (footprint "Test_Point")
      (libsource (lib "hand_ad_lib") (part "Test_Point"))
    )
    (comp (ref "TP36")
      (value "Test point")
      (footprint "Test_Point")
      (libsource (lib "hand_ad_lib") (part "Test_Point"))
    )
    (comp (ref "TP37")
      (value "Test point")
      (footprint "Test_Point")
      (libsource (lib "hand_ad_lib") (part "Test_Point"))
    )
    (comp (ref "TP42")
      (value "Test point")
      (footprint "Test_Point")
      (libsource (lib "hand_ad_lib") (part "Test_Point"))
    )
    (comp (ref "TP43")
      (value "Test point")
      (footprint "Test_Point")
      (libsource (lib "hand_ad_lib") (part "Test_Point"))
    )
    (comp (ref "U23")
      (value "ESP32-S3-MINI-1-N8")
      (footprint "XCVR_ESP32-S3-MINI-1-N8")
      (description "Bluetooth, WiFi 802.11b/g/n, Bluetooth v5.0 Transceiver Module 2.4GHz PCB Trace Surface Mount")
      (fields (field (name "MF") "Espressif Systems"))
      (libsource (lib "hand_ad_lib") (part "ESP32-S3-MINI-1-N8"))
    )
    (comp (ref "U24")
      (value "TXB0104YZTR")
      (footprint "FP-YZT0012-IPC_B")
      (description "I2C Level Shifter 4 channel, IC TRNSLTR BIDIRECTIONAL 12DSBGA")
      (libsource (lib "hand_ad_lib") (part "TXB0104YZTR"))
    )
    (comp (ref "U25")
      (value "TXS0102DQER")
      (footprint "FP-DQE0008A-IPC_C")
      (fields
        (field (name "OCTOPART") "https://octopart.com/txs0102dqer-texas+instruments-19973770")
        (field (name "MANUFACTURER") "Texas Instruments")
      )
      (libsource (lib "hand_ad_lib") (part "TXS0102DQER"))
    )
    (comp (ref "U26")
      (value "TCA6408ARGTR")
      (footprint "RGT0016A_V")
      (fields (field (name "MANUFACTURER") "Texas Instruments"))
      (libsource (lib "hand_ad_lib") (part "TCA6408ARGTR"))
    )
    (comp (ref "U27")
      (value "TCA6408ARGTR")
      (footprint "RGT0016A_V")
      (fields (field (name "MANUFACTURER") "Texas Instruments"))
      (libsource (lib "hand_ad_lib") (part "TCA6408ARGTR"))
    )
    (comp (ref "U28")
      (value "BOS1901CWR")
      (footprint "BOS1901_BGA25C40P5X5_212X224X66")
      (libsource (lib "hand_ad_lib") (part "BOS1901CWR"))
    )
    (comp (ref "U29")
      (value "BOS1901CWR")
      (footprint "BOS1901_BGA25C40P5X5_212X224X66")
      (libsource (lib "hand_ad_lib") (part "BOS1901CWR"))
    )
    (comp (ref "U30")
      (value "BOS1901CWR")
      (footprint "BOS1901_BGA25C40P5X5_212X224X66")
      (libsource (lib "hand_ad_lib") (part "BOS1901CWR"))
    )
    (comp (ref "U31")
      (value "BOS1901CWR")
      (footprint "BOS1901_BGA25C40P5X5_212X224X66")
      (libsource (lib "hand_ad_lib") (part "BOS1901CWR"))
    )
    (comp (ref "X1")
      (value "32.768kHz")
      (footprint "OSC-SMD_4P-L2.5-W2.0-BL")
      (fields
        (field (name "MANUFACTURER") "YXC(扬兴晶振)")
        (field (name "MANUFACTURER PART") "OK252032.768KJBA4SL")
        (field (name "NAME") "32.768kHz")
      )
      (libsource (lib "hand_ad_lib") (part "OK252032.768KJBA4SL"))
    )
  )
  (nets
    (net (code "1") (name "+1.8V") (class "Default")
      (node (ref "C58") (pin "1") (pinfunction "1_1") (pintype "passive"))
      (node (ref "C59") (pin "1") (pinfunction "1_1") (pintype "passive"))
      (node (ref "C65") (pin "1") (pinfunction "1_1") (pintype "passive"))
      (node (ref "J4") (pin "19") (pinfunction "19_19") (pintype "passive"))
      (node (ref "J5") (pin "4") (pinfunction "4_4") (pintype "passive"))
      (node (ref "J5") (pin "42") (pinfunction "42_42") (pintype "passive"))
      (node (ref "R55") (pin "1") (pinfunction "1_1") (pintype "passive"))
      (node (ref "R56") (pin "2") (pinfunction "2_2") (pintype "passive"))
      (node (ref "R58") (pin "1") (pinfunction "1_1") (pintype "passive"))
      (node (ref "R59") (pin "2") (pinfunction "2_2") (pintype "passive"))
      (node (ref "U24") (pin "B2") (pinfunction "VCCA_B2") (pintype "power_in"))
      (node (ref "U24") (pin "C2") (pinfunction "OE_C2") (pintype "input"))
      (node (ref "U25") (pin "1") (pinfunction "VCCA_1") (pintype "power_in"))
      (node (ref "U25") (pin "5") (pinfunction "OE_5") (pintype "input"))
      (node (ref "U27") (pin "14") (pinfunction "VCCP_14") (pintype "power_in"))
    )
    (net (code "2") (name "+3.3V") (class "Default")
      (node (ref "C48") (pin "2") (pinfunction "2_2") (pintype "passive"))
      (node (ref "C51") (pin "2") (pinfunction "2_2") (pintype "passive"))
      (node (ref "C53") (pin "2") (pinfunction "2_2") (pintype "passive"))
      (node (ref "C54") (pin "2") (pinfunction "2_2") (pintype "passive"))
      (node (ref "C55") (pin "2") (pinfunction "2_2") (pintype "passive"))
      (node (ref "C56") (pin "2") (pinfunction "2_2") (pintype "passive"))
      (node (ref "C57") (pin "2") (pinfunction "2_2") (pintype "passive"))
      (node (ref "C60") (pin "1") (pinfunction "1_1") (pintype "passive"))
      (node (ref "C61") (pin "2") (pinfunction "2_2") (pintype "passive"))
      (node (ref "C62") (pin "1") (pinfunction "1_1") (pintype "passive"))
      (node (ref "C63") (pin "1") (pinfunction "1_1") (pintype "passive"))
      (node (ref "C64") (pin "1") (pinfunction "1_1") (pintype "passive"))
      (node (ref "C71") (pin "2") (pinfunction "2_2") (pintype "passive"))
      (node (ref "C72") (pin "2") (pinfunction "2_2") (pintype "passive"))
      (node (ref "C81") (pin "2") (pinfunction "2_2") (pintype "passive"))
      (node (ref "C82") (pin "2") (pinfunction "2_2") (pintype "passive"))
      (node (ref "J4") (pin "17") (pinfunction "17_17") (pintype "passive"))
      (node (ref "J5") (pin "3") (pinfunction "3_3") (pintype "passive"))
      (node (ref "J5") (pin "43") (pinfunction "43_43") (pintype "passive"))
      (node (ref "LED4") (pin "1") (pinfunction "VDD_1") (pintype "power_in"))
      (node (ref "R39") (pin "2") (pinfunction "2_2") (pintype "passive"))
      (node (ref "R42") (pin "2") (pinfunction "2_2") (pintype "passive"))
      (node (ref "R43") (pin "1") (pinfunction "1_1") (pintype "passive"))
      (node (ref "R48") (pin "2") (pinfunction "2_2") (pintype "passive"))
      (node (ref "R49") (pin "2") (pinfunction "2_2") (pintype "passive"))
      (node (ref "R60") (pin "1") (pinfunction "1_1") (pintype "passive"))
      (node (ref "R61") (pin "1") (pinfunction "1_1") (pintype "passive"))
      (node (ref "TP42") (pin "TP?") (pinfunction "Test_point_TP?") (pintype "passive"))
      (node (ref "U23") (pin "3") (pinfunction "3V3_3") (pintype "power_in"))
      (node (ref "U24") (pin "A2") (pinfunction "VCCB_A2") (pintype "power_in"))
      (node (ref "U25") (pin "8") (pinfunction "VCCB_8") (pintype "power_in"))
      (node (ref "U26") (pin "1") (pinfunction "~{RESET}_1") (pintype "input"))
      (node (ref "U26") (pin "14") (pinfunction "VCCP_14") (pintype "power_in"))
      (node (ref "U26") (pin "15") (pinfunction "VCCI_15") (pintype "power_in"))
      (node (ref "U27") (pin "1") (pinfunction "~{RESET}_1") (pintype "input"))
      (node (ref "U27") (pin "15") (pinfunction "VCCI_15") (pintype "power_in"))
      (node (ref "U27") (pin "16") (pinfunction "ADDR_16") (pintype "input"))
      (node (ref "U28") (pin "C4") (pinfunction "TST1_C4") (pintype "passive"))
      (node (ref "U28") (pin "D2") (pinfunction "TST2_D2") (pintype "passive"))
      (node (ref "U28") (pin "D3") (pinfunction "TST3_D3") (pintype "passive"))
      (node (ref "U28") (pin "E4") (pinfunction "VDDIO_E4") (pintype "power_in"))
      (node (ref "U29") (pin "C4") (pinfunction "TST1_C4") (pintype "passive"))
      (node (ref "U29") (pin "D2") (pinfunction "TST2_D2") (pintype "passive"))
      (node (ref "U29") (pin "D3") (pinfunction "TST3_D3") (pintype "passive"))
      (node (ref "U29") (pin "E4") (pinfunction "VDDIO_E4") (pintype "power_in"))
      (node (ref "U30") (pin "C4") (pinfunction "TST1_C4") (pintype "passive"))
      (node (ref "U30") (pin "D2") (pinfunction "TST2_D2") (pintype "passive"))
      (node (ref "U30") (pin "D3") (pinfunction "TST3_D3") (pintype "passive"))
      (node (ref "U30") (pin "E4") (pinfunction "VDDIO_E4") (pintype "power_in"))
      (node (ref "U31") (pin "C4") (pinfunction "TST1_C4") (pintype "passive"))
      (node (ref "U31") (pin "D2") (pinfunction "TST2_D2") (pintype "passive"))
      (node (ref "U31") (pin "D3") (pinfunction "TST3_D3") (pintype "passive"))
      (node (ref "U31") (pin "E4") (pinfunction "VDDIO_E4") (pintype "power_in"))
      (node (ref "X1") (pin "4") (pinfunction "VDD_4") (pintype "passive"))
    )
    (net (code "3") (name "+5V") (class "Default")
      (node (ref "U28") (pin "A2") (pinfunction "VBUS_A2") (pintype "power_in"))
      (node (ref "U29") (pin "A2") (pinfunction "VBUS_A2") (pintype "power_in"))
      (node (ref "U30") (pin "A2") (pinfunction "VBUS_A2") (pintype "power_in"))
      (node (ref "U31") (pin "A2") (pinfunction "VBUS_A2") (pintype "power_in"))
    )
    (net (code "4") (name "+VBUS") (class "Default")
      (node (ref "J4") (pin "18") (pinfunction "18_18") (pintype "passive"))
      (node (ref "R54") (pin "1") (pinfunction "1_1") (pintype "passive"))
    )
    (net (code "5") (name "/BAT_INSERT_DETECT") (class "Default")
      (node (ref "C66") (pin "2") (pinfunction "2_2") (pintype "passive"))
      (node (ref "R51") (pin "2") (pinfunction "2_2") (pintype "passive"))
      (node (ref "TP30") (pin "TP?") (pinfunction "Test_point_TP?") (pintype "passive"))
      (node (ref "U26") (pin "10") (pinfunction "P7_10") (pintype "bidirectional"))
    )
    (net (code "6") (name "/BOS1901_1_CS") (class "Default")
      (node (ref "U23") (pin "14") (pinfunction "IO10_14") (pintype "bidirectional"))
      (node (ref "U28") (pin "D4") (pinfunction "~{CS}_D4") (pintype "input"))
    )
    (net (code "7") (name "/BOS1901_2_CS") (class "Default")
      (node (ref "U23") (pin "13") (pinfunction "IO9_13") (pintype "bidirectional"))
      (node (ref "U30") (pin "D4") (pinfunction "~{CS}_D4") (pintype "input"))
    )
    (net (code "8") (name "/BOS1901_3_CS") (class "Default")
      (node (ref "U23") (pin "12") (pinfunction "IO8_12") (pintype "bidirectional"))
      (node (ref "U29") (pin "D4") (pinfunction "~{CS}_D4") (pintype "input"))
    )
    (net (code "9") (name "/BOS1901_4_CS") (class "Default")
      (node (ref "U23") (pin "11") (pinfunction "IO7_11") (pintype "bidirectional"))
      (node (ref "U31") (pin "D4") (pinfunction "~{CS}_D4") (pintype "input"))
    )
    (net (code "10") (name "/BQ25302_STAT") (class "Default")
      (node (ref "U26") (pin "4") (pinfunction "P2_4") (pintype "bidirectional"))
    )
    (net (code "11") (name "/BQ27427_GPOUT") (class "Default")
      (node (ref "U26") (pin "2") (pinfunction "P0_2") (pintype "bidirectional"))
    )
    (net (code "12") (name "/DEBUG_P1_TX") (class "Default")
      (node (ref "J4") (pin "11") (pinfunction "11_11") (pintype "passive"))
      (node (ref "R34") (pin "1") (pinfunction "1_1") (pintype "passive"))
      (node (ref "U23") (pin "39") (pinfunction "TXD0_39") (pintype "bidirectional"))
    )
    (net (code "13") (name "/DEBUG_P2_RX") (class "Default")
      (node (ref "J4") (pin "13") (pinfunction "13_13") (pintype "passive"))
      (node (ref "R35") (pin "1") (pinfunction "1_1") (pintype "passive"))
      (node (ref "U23") (pin "40") (pinfunction "RXD0_40") (pintype "bidirectional"))
    )
    (net (code "14") (name "/DEBUG_P3_RGB") (class "Default")
      (node (ref "J4") (pin "12") (pinfunction "12_12") (pintype "passive"))
      (node (ref "LED4") (pin "4") (pinfunction "DIN_4") (pintype "input"))
      (node (ref "R38") (pin "2") (pinfunction "2_2") (pintype "passive"))
      (node (ref "U23") (pin "41") (pinfunction "IO45_41") (pintype "bidirectional"))
    )
    (net (code "15") (name "/DEBUG_P4") (class "Default")
      (node (ref "J4") (pin "14") (pinfunction "14_14") (pintype "passive"))
      (node (ref "R37") (pin "2") (pinfunction "2_2") (pintype "passive"))
      (node (ref "U23") (pin "44") (pinfunction "IO46_44") (pintype "bidirectional"))
    )
    (net (code "16") (name "/ESP_CH101_SCL") (class "Default")
      (node (ref "U23") (pin "6") (pinfunction "IO2_6") (pintype "bidirectional"))
      (node (ref "U25") (pin "7") (pinfunction "B1_7") (pintype "bidirectional"))
    )
    (net (code "17") (name "/ESP_CH101_SDA") (class "Default")
      (node (ref "U23") (pin "7") (pinfunction "IO3_7") (pintype "bidirectional"))
      (node (ref "U25") (pin "6") (pinfunction "B2_6") (pintype "bidirectional"))
    )
    (net (code "18") (name "/ESP_EN") (class "Default")
      (node (ref "C49") (pin "1") (pinfunction "1_1") (pintype "passive"))
      (node (ref "J4") (pin "15") (pinfunction "15_15") (pintype "passive"))
      (node (ref "R40") (pin "2") (pinfunction "2_2") (pintype "passive"))
      (node (ref "R43") (pin "2") (pinfunction "2_2") (pintype "passive"))
      (node (ref "TP26") (pin "TP?") (pinfunction "Test_point_TP?") (pintype "passive"))
      (node (ref "U23") (pin "45") (pinfunction "EN_45") (pintype "input"))
    )
    (net (code "19") (name "/ESP_USB_N") (class "Default")
      (node (ref "R44") (pin "2") (pinfunction "2_2") (pintype "passive"))
    )
    (net (code "20") (name "/ESP_USB_P") (class "Default")
      (node (ref "R45") (pin "2") (pinfunction "2_2") (pintype "passive"))
    )
    (net (code "21") (name "/FPC_BMI323_CS") (class "Default")
      (node (ref "J5") (pin "23") (pinfunction "23_23") (pintype "passive"))
      (node (ref "U23") (pin "9") (pinfunction "IO5_9") (pintype "bidirectional"))
    )
    (net (code "22") (name "/FPC_BMI323_INT1") (class "Default")
      (node (ref "J5") (pin "24") (pinfunction "24_24") (pintype "passive"))
      (node (ref "U23") (pin "8") (pinfunction "IO4_8") (pintype "bidirectional"))
    )
    (net (code "23") (name "/FPC_BMI323_INT2") (class "Default")
      (node (ref "J5") (pin "22") (pinfunction "22_22") (pintype "passive"))
      (node (ref "R60") (pin "2") (pinfunction "2_2") (pintype "passive"))
      (node (ref "U26") (pin "7") (pinfunction "P4_7") (pintype "bidirectional"))
    )
    (net (code "24") (name "/FPC_BOARD_SCL") (class "Default")
      (node (ref "J4") (pin "7") (pinfunction "7_7") (pintype "passive"))
      (node (ref "J5") (pin "38") (pinfunction "38_38") (pintype "passive"))
      (node (ref "R42") (pin "1") (pinfunction "1_1") (pintype "passive"))
      (node (ref "SW5") (pin "2") (pinfunction "B_2") (pintype "passive"))
      (node (ref "TP25") (pin "TP?") (pinfunction "Test_point_TP?") (pintype "passive"))
      (node (ref "U23") (pin "4") (pinfunction "IO0_4") (pintype "bidirectional"))
      (node (ref "U26") (pin "12") (pinfunction "SCL_12") (pintype "input"))
      (node (ref "U27") (pin "12") (pinfunction "SCL_12") (pintype "input"))
    )
    (net (code "25") (name "/FPC_BOARD_SDA") (class "Default")
      (node (ref "J4") (pin "9") (pinfunction "9_9") (pintype "passive"))
      (node (ref "J5") (pin "37") (pinfunction "37_37") (pintype "passive"))
      (node (ref "R39") (pin "1") (pinfunction "1_1") (pintype "passive"))
      (node (ref "U23") (pin "5") (pinfunction "IO1_5") (pintype "bidirectional"))
      (node (ref "U26") (pin "13") (pinfunction "SDA_13") (pintype "bidirectional"))
      (node (ref "U27") (pin "13") (pinfunction "SDA_13") (pintype "bidirectional"))
    )
    (net (code "26") (name "/FPC_BOS1901_1_OUT+") (class "Default")
      (node (ref "J3") (pin "16") (pinfunction "16_16") (pintype "passive"))
      (node (ref "J3") (pin "17") (pinfunction "17_17") (pintype "passive"))
      (node (ref "J3") (pin "18") (pinfunction "18_18") (pintype "passive"))
      (node (ref "TP34") (pin "TP?") (pinfunction "Test_point_TP?") (pintype "passive"))
      (node (ref "U28") (pin "B1") (pinfunction "OUT+_B1") (pintype "output"))
    )
    (net (code "27") (name "/FPC_BOS1901_1_OUT−") (class "Default")
      (node (ref "J3") (pin "13") (pinfunction "13_13") (pintype "passive"))
      (node (ref "J3") (pin "14") (pinfunction "14_14") (pintype "passive"))
      (node (ref "J3") (pin "15") (pinfunction "15_15") (pintype "passive"))
      (node (ref "TP35") (pin "TP?") (pinfunction "Test_point_TP?") (pintype "passive"))
      (node (ref "U28") (pin "C1") (pinfunction "OUT−_C1") (pintype "output"))
    )
    (net (code "28") (name "/FPC_BOS1901_2_OUT+") (class "Default")
      (node (ref "J3") (pin "22") (pinfunction "22_22") (pintype "passive"))
      (node (ref "J3") (pin "23") (pinfunction "23_23") (pintype "passive"))
      (node (ref "J3") (pin "24") (pinfunction "24_24") (pintype "passive"))
      (node (ref "U30") (pin "B1") (pinfunction "OUT+_B1") (pintype "output"))
    )
    (net (code "29") (name "/FPC_BOS1901_2_OUT−") (class "Default")
      (node (ref "J3") (pin "19") (pinfunction "19_19") (pintype "passive"))
      (node (ref "J3") (pin "20") (pinfunction "20_20") (pintype "passive"))
      (node (ref "J3") (pin "21") (pinfunction "21_21") (pintype "passive"))
      (node (ref "U30") (pin "C1") (pinfunction "OUT−_C1") (pintype "output"))
    )
    (net (code "30") (name "/FPC_BOS1901_3_OUT+") (class "Default")
      (node (ref "J3") (pin "1") (pinfunction "1_1") (pintype "passive"))
      (node (ref "J3") (pin "2") (pinfunction "2_2") (pintype "passive"))
      (node (ref "J3") (pin "3") (pinfunction "3_3") (pintype "passive"))
      (node (ref "U29") (pin "B1") (pinfunction "OUT+_B1") (pintype "output"))
    )
    (net (code "31") (name "/FPC_BOS1901_3_OUT−") (class "Default")
      (node (ref "J3") (pin "4") (pinfunction "4_4") (pintype "passive"))
      (node (ref "J3") (pin "5") (pinfunction "5_5") (pintype "passive"))
      (node (ref "J3") (pin "6") (pinfunction "6_6") (pintype "passive"))
      (node (ref "U29") (pin "C1") (pinfunction "OUT−_C1") (pintype "output"))
    )
    (net (code "32") (name "/FPC_BOS1901_4_OUT+") (class "Default")
      (node (ref "J3") (pin "7") (pinfunction "7_7") (pintype "passive"))
      (node (ref "J3") (pin "8") (pinfunction "8_8") (pintype "passive"))
      (node (ref "J3") (pin "9") (pinfunction "9_9") (pintype "passive"))
      (node (ref "U31") (pin "B1") (pinfunction "OUT+_B1") (pintype "output"))
    )
    (net (code "33") (name "/FPC_BOS1901_4_OUT−") (class "Default")
      (node (ref "J3") (pin "10") (pinfunction "10_10") (pintype "passive"))
      (node (ref "J3") (pin "11") (pinfunction "11_11") (pintype "passive"))
      (node (ref "J3") (pin "12") (pinfunction "12_12") (pintype "passive"))
      (node (ref "U31") (pin "C1") (pinfunction "OUT−_C1") (pintype "output"))
    )
    (net (code "34") (name "/FPC_CH101_1_INT") (class "Default")
      (node (ref "J5") (pin "16") (pinfunction "16_16") (pintype "passive"))
      (node (ref "U24") (pin "A3") (pinfunction "A1_A3") (pintype "bidirectional"))
    )
    (net (code "35") (name "/FPC_CH101_1_PROG") (class "Default")
      (node (ref "J5") (pin "14") (pinfunction "14_14") (pintype "passive"))
      (node (ref "U27") (pin "2") (pinfunction "P0_2") (pintype "bidirectional"))
    )
    (net (code "36") (name "/FPC_CH101_1_RESET") (class "Default")
      (node (ref "J5") (pin "15") (pinfunction "15_15") (pintype "passive"))
      (node (ref "R58") (pin "2") (pinfunction "2_2") (pintype "passive"))
      (node (ref "TP28") (pin "TP?") (pinfunction "Test_point_TP?") (pintype "passive"))
      (node (ref "U27") (pin "3") (pinfunction "P1_3") (pintype "bidirectional"))
    )
    (net (code "37") (name "/FPC_CH101_2_INT") (class "Default")
      (node (ref "J5") (pin "19") (pinfunction "19_19") (pintype "passive"))
      (node (ref "U24") (pin "B3") (pinfunction "A2_B3") (pintype "bidirectional"))
    )
    (net (code "38") (name "/FPC_CH101_2_PROG") (class "Default")
      (node (ref "J5") (pin "17") (pinfunction "17_17") (pintype "passive"))
      (node (ref "U27") (pin "4") (pinfunction "P2_4") (pintype "bidirectional"))
    )
    (net (code "39") (name "/FPC_CH101_2_RESET") (class "Default")
      (node (ref "J5") (pin "18") (pinfunction "18_18") (pintype "passive"))
      (node (ref "R55") (pin "2") (pinfunction "2_2") (pintype "passive"))
      (node (ref "U27") (pin "5") (pinfunction "P3_5") (pintype "bidirectional"))
    )
    (net (code "40") (name "/FPC_CH101_3_INT") (class "Default")
      (node (ref "J5") (pin "27") (pinfunction "27_27") (pintype "passive"))
      (node (ref "U24") (pin "C3") (pinfunction "A3_C3") (pintype "bidirectional"))
    )
    (net (code "41") (name "/FPC_CH101_3_PROG") (class "Default")
      (node (ref "J5") (pin "29") (pinfunction "29_29") (pintype "passive"))
      (node (ref "U27") (pin "7") (pinfunction "P4_7") (pintype "bidirectional"))
    )
    (net (code "42") (name "/FPC_CH101_3_RESET") (class "Default")
      (node (ref "J5") (pin "28") (pinfunction "28_28") (pintype "passive"))
      (node (ref "R56") (pin "1") (pinfunction "1_1") (pintype "passive"))
      (node (ref "U27") (pin "8") (pinfunction "P5_8") (pintype "bidirectional"))
    )
    (net (code "43") (name "/FPC_CH101_4_INT") (class "Default")
      (node (ref "J5") (pin "30") (pinfunction "30_30") (pintype "passive"))
      (node (ref "U24") (pin "D3") (pinfunction "A4_D3") (pintype "bidirectional"))
    )
    (net (code "44") (name "/FPC_CH101_4_PROG") (class "Default")
      (node (ref "J5") (pin "32") (pinfunction "32_32") (pintype "passive"))
      (node (ref "U27") (pin "9") (pinfunction "P6_9") (pintype "bidirectional"))
    )
    (net (code "45") (name "/FPC_CH101_4_RESET") (class "Default")
      (node (ref "J5") (pin "31") (pinfunction "31_31") (pintype "passive"))
      (node (ref "R59") (pin "1") (pinfunction "1_1") (pintype "passive"))
      (node (ref "U27") (pin "10") (pinfunction "P7_10") (pintype "bidirectional"))
    )
    (net (code "46") (name "/FPC_CH101_SCL") (class "Default")
      (node (ref "J4") (pin "8") (pinfunction "8_8") (pintype "passive"))
      (node (ref "J5") (pin "8") (pinfunction "8_8") (pintype "passive"))
      (node (ref "U25") (pin "2") (pinfunction "A1_2") (pintype "bidirectional"))
    )
    (net (code "47") (name "/FPC_CH101_SDA") (class "Default")
      (node (ref "J4") (pin "10") (pinfunction "10_10") (pintype "passive"))
      (node (ref "J5") (pin "9") (pinfunction "9_9") (pintype "passive"))
      (node (ref "U25") (pin "3") (pinfunction "A2_3") (pintype "bidirectional"))
    )
    (net (code "48") (name "/FPC_KX132_1_CS") (class "Default")
      (node (ref "J5") (pin "10") (pinfunction "10_10") (pintype "passive"))
      (node (ref "U23") (pin "10") (pinfunction "IO6_10") (pintype "bidirectional"))
    )
    (net (code "49") (name "/FPC_KX132_1_INT1") (class "Default")
      (node (ref "J5") (pin "11") (pinfunction "11_11") (pintype "passive"))
      (node (ref "U23") (pin "29") (pinfunction "IO34_29") (pintype "bidirectional"))
    )
    (net (code "50") (name "/FPC_KX132_2_CS") (class "Default")
      (node (ref "J5") (pin "12") (pinfunction "12_12") (pintype "passive"))
      (node (ref "U23") (pin "35") (pinfunction "IO39_35") (pintype "bidirectional"))
    )
    (net (code "51") (name "/FPC_KX132_2_INT1") (class "Default")
      (node (ref "J5") (pin "13") (pinfunction "13_13") (pintype "passive"))
      (node (ref "U23") (pin "34") (pinfunction "IO38_34") (pintype "bidirectional"))
    )
    (net (code "52") (name "/FPC_KX132_3_CS") (class "Default")
      (node (ref "J5") (pin "34") (pinfunction "34_34") (pintype "passive"))
      (node (ref "U23") (pin "33") (pinfunction "IO37_33") (pintype "bidirectional"))
    )
    (net (code "53") (name "/FPC_KX132_3_INT1") (class "Default")
      (node (ref "J5") (pin "33") (pinfunction "33_33") (pintype "passive"))
      (node (ref "U23") (pin "32") (pinfunction "IO36_32") (pintype "bidirectional"))
    )
    (net (code "54") (name "/FPC_KX132_4_CS") (class "Default")
      (node (ref "J5") (pin "36") (pinfunction "36_36") (pintype "passive"))
      (node (ref "U23") (pin "31") (pinfunction "IO35_31") (pintype "bidirectional"))
    )
    (net (code "55") (name "/FPC_KX132_4_INT1") (class "Default")
      (node (ref "J5") (pin "35") (pinfunction "35_35") (pintype "passive"))
      (node (ref "U23") (pin "30") (pinfunction "IO48_30") (pintype "bidirectional"))
    )
    (net (code "56") (name "/FPC_SPI2_SCLK") (class "Default")
      (node (ref "J4") (pin "3") (pinfunction "3_3") (pintype "passive"))
      (node (ref "J5") (pin "40") (pinfunction "40_40") (pintype "passive"))
      (node (ref "R41") (pin "1") (pinfunction "1_1") (pintype "passive"))
      (node (ref "U28") (pin "E5") (pinfunction "SCLK_E5") (pintype "input"))
      (node (ref "U29") (pin "E5") (pinfunction "SCLK_E5") (pintype "input"))
      (node (ref "U30") (pin "E5") (pinfunction "SCLK_E5") (pintype "input"))
      (node (ref "U31") (pin "E5") (pinfunction "SCLK_E5") (pintype "input"))
    )
    (net (code "57") (name "/FPC_SPI2_SDI") (class "Default")
      (node (ref "J4") (pin "5") (pinfunction "5_5") (pintype "passive"))
      (node (ref "J5") (pin "41") (pinfunction "41_41") (pintype "passive"))
      (node (ref "R36") (pin "1") (pinfunction "1_1") (pintype "passive"))
      (node (ref "U28") (pin "D5") (pinfunction "SDI_D5") (pintype "input"))
      (node (ref "U29") (pin "D5") (pinfunction "SDI_D5") (pintype "input"))
      (node (ref "U30") (pin "D5") (pinfunction "SDI_D5") (pintype "input"))
      (node (ref "U31") (pin "D5") (pinfunction "SDI_D5") (pintype "input"))
    )
    (net (code "58") (name "/FPC_SPI2_SDO") (class "Default")
      (node (ref "J4") (pin "1") (pinfunction "1_1") (pintype "passive"))
      (node (ref "J5") (pin "39") (pinfunction "39_39") (pintype "passive"))
      (node (ref "R62") (pin "1") (pinfunction "1_1") (pintype "passive"))
      (node (ref "R63") (pin "1") (pinfunction "1_1") (pintype "passive"))
      (node (ref "R66") (pin "1") (pinfunction "1_1") (pintype "passive"))
      (node (ref "R67") (pin "1") (pinfunction "1_1") (pintype "passive"))
      (node (ref "U23") (pin "15") (pinfunction "IO11_15") (pintype "bidirectional"))
    )
    (net (code "59") (name "/FPC_SPI3_SCLK") (class "Default")
      (node (ref "J4") (pin "4") (pinfunction "4_4") (pintype "passive"))
      (node (ref "J5") (pin "6") (pinfunction "6_6") (pintype "passive"))
      (node (ref "R46") (pin "2") (pinfunction "2_2") (pintype "passive"))
    )
    (net (code "60") (name "/FPC_SPI3_SDI") (class "Default")
      (node (ref "J4") (pin "6") (pinfunction "6_6") (pintype "passive"))
      (node (ref "J5") (pin "5") (pinfunction "5_5") (pintype "passive"))
      (node (ref "R47") (pin "2") (pinfunction "2_2") (pintype "passive"))
    )
    (net (code "61") (name "/FPC_SPI3_SDO") (class "Default")
      (node (ref "J4") (pin "2") (pinfunction "2_2") (pintype "passive"))
      (node (ref "J5") (pin "7") (pinfunction "7_7") (pintype "passive"))
      (node (ref "U23") (pin "36") (pinfunction "IO40_36") (pintype "bidirectional"))
    )
    (net (code "62") (name "/FPC_VL53L1X_1_GPIO1") (class "Default")
      (node (ref "J5") (pin "20") (pinfunction "20_20") (pintype "passive"))
      (node (ref "U23") (pin "21") (pinfunction "IO17_21") (pintype "bidirectional"))
    )
    (net (code "63") (name "/FPC_VL53L1X_1_XSHUT") (class "Default")
      (node (ref "J5") (pin "21") (pinfunction "21_21") (pintype "passive"))
      (node (ref "R61") (pin "2") (pinfunction "2_2") (pintype "passive"))
      (node (ref "TP31") (pin "TP?") (pinfunction "Test_point_TP?") (pintype "passive"))
      (node (ref "U26") (pin "5") (pinfunction "P3_5") (pintype "bidirectional"))
    )
    (net (code "64") (name "/FPC_VL53L1X_2_GPIO1") (class "Default")
      (node (ref "J5") (pin "26") (pinfunction "26_26") (pintype "passive"))
      (node (ref "U23") (pin "22") (pinfunction "IO18_22") (pintype "bidirectional"))
    )
    (net (code "65") (name "/FPC_VL53L1X_2_XSHUT") (class "Default")
      (node (ref "J5") (pin "25") (pinfunction "25_25") (pintype "passive"))
      (node (ref "R57") (pin "2") (pinfunction "2_2") (pintype "passive"))
      (node (ref "TP29") (pin "TP?") (pinfunction "Test_point_TP?") (pintype "passive"))
      (node (ref "U26") (pin "8") (pinfunction "P5_8") (pintype "bidirectional"))
    )
    (net (code "66") (name "/TCA_BQ25302_EN") (class "Default")
      (node (ref "U26") (pin "3") (pinfunction "P1_3") (pintype "bidirectional"))
    )
    (net (code "67") (name "/TCA_INT") (class "Default")
      (node (ref "R48") (pin "1") (pinfunction "1_1") (pintype "passive"))
      (node (ref "TP27") (pin "TP?") (pinfunction "Test_point_TP?") (pintype "passive"))
      (node (ref "U23") (pin "18") (pinfunction "IO14_18") (pintype "bidirectional"))
      (node (ref "U26") (pin "11") (pinfunction "~{INT}_11") (pintype "open_collector"))
    )
    (net (code "68") (name "/TXB0104_B1") (class "Default")
      (node (ref "U23") (pin "28") (pinfunction "IO33_28") (pintype "bidirectional"))
      (node (ref "U24") (pin "A1") (pinfunction "B1_A1") (pintype "bidirectional"))
    )
    (net (code "69") (name "/TXB0104_B2") (class "Default")
      (node (ref "U23") (pin "27") (pinfunction "IO47_27") (pintype "bidirectional"))
      (node (ref "U24") (pin "B1") (pinfunction "B2_B1") (pintype "bidirectional"))
    )
    (net (code "70") (name "/TXB0104_B3") (class "Default")
      (node (ref "U23") (pin "26") (pinfunction "IO26_26") (pintype "bidirectional"))
      (node (ref "U24") (pin "C1") (pinfunction "B3_C1") (pintype "bidirectional"))
    )
    (net (code "71") (name "/TXB0104_B4") (class "Default")
      (node (ref "U23") (pin "25") (pinfunction "IO21_25") (pintype "bidirectional"))
      (node (ref "U24") (pin "D1") (pinfunction "B4_D1") (pintype "bidirectional"))
    )
    (net (code "72") (name "/USB_RES_N") (class "Default")
      (node (ref "R44") (pin "1") (pinfunction "1_1") (pintype "passive"))
      (node (ref "U23") (pin "23") (pinfunction "IO19_23") (pintype "bidirectional"))
    )
    (net (code "73") (name "/USB_RES_P") (class "Default")
      (node (ref "R45") (pin "1") (pinfunction "1_1") (pintype "passive"))
      (node (ref "U23") (pin "24") (pinfunction "IO20_24") (pintype "bidirectional"))
    )
    (net (code "74") (name "/VBUS_INSERT_DETECT") (class "Default")
      (node (ref "R54") (pin "2") (pinfunction "2_2") (pintype "passive"))
      (node (ref "U26") (pin "9") (pinfunction "P6_9") (pintype "bidirectional"))
    )
    (net (code "75") (name "BAT+") (class "Default")
      (node (ref "J4") (pin "16") (pinfunction "16_16") (pintype "passive"))
      (node (ref "R50") (pin "2") (pinfunction "2_2") (pintype "passive"))
      (node (ref "R51") (pin "1") (pinfunction "1_1") (pintype "passive"))
    )
    (net (code "76") (name "GND") (class "Default")
      (node (ref "C48") (pin "1") (pinfunction "1_1") (pintype "passive"))
      (node (ref "C49") (pin "2") (pinfunction "2_2") (pintype "passive"))
      (node (ref "C50") (pin "2") (pinfunction "2_2") (pintype "passive"))
      (node (ref "C51") (pin "1") (pinfunction "1_1") (pintype "passive"))
      (node (ref "C53") (pin "1") (pinfunction "1_1") (pintype "passive"))
      (node (ref "C54") (pin "1") (pinfunction "1_1") (pintype "passive"))
      (node (ref "C55") (pin "1") (pinfunction "1_1") (pintype "passive"))
      (node (ref "C56") (pin "1") (pinfunction "1_1") (pintype "passive"))
      (node (ref "C57") (pin "1") (pinfunction "1_1") (pintype "passive"))
      (node (ref "C58") (pin "2") (pinfunction "2_2") (pintype "passive"))
      (node (ref "C59") (pin "2") (pinfunction "2_2") (pintype "passive"))
      (node (ref "C60") (pin "2") (pinfunction "2_2") (pintype "passive"))
      (node (ref "C61") (pin "1") (pinfunction "1_1") (pintype "passive"))
      (node (ref "C62") (pin "2") (pinfunction "2_2") (pintype "passive"))
      (node (ref "C63") (pin "2") (pinfunction "2_2") (pintype "passive"))
      (node (ref "C64") (pin "2") (pinfunction "2_2") (pintype "passive"))
      (node (ref "C65") (pin "2") (pinfunction "2_2") (pintype "passive"))
      (node (ref "C66") (pin "1") (pinfunction "1_1") (pintype "passive"))
      (node (ref "C67") (pin "2") (pinfunction "2_2") (pintype "passive"))
      (node (ref "C68") (pin "2") (pinfunction "2_2") (pintype "passive"))
      (node (ref "C69") (pin "1") (pinfunction "1_1") (pintype "passive"))
      (node (ref "C70") (pin "1") (pinfunction "1_1") (pintype "passive"))
      (node (ref "C71") (pin "1") (pinfunction "1_1") (pintype "passive"))
      (node (ref "C72") (pin "1") (pinfunction "1_1") (pintype "passive"))
      (node (ref "C75") (pin "1") (pinfunction "1_1") (pintype "passive"))
      (node (ref "C76") (pin "1") (pinfunction "1_1") (pintype "passive"))
      (node (ref "C77") (pin "2") (pinfunction "2_2") (pintype "passive"))
      (node (ref "C78") (pin "2") (pinfunction "2_2") (pintype "passive"))
      (node (ref "C79") (pin "1") (pinfunction "1_1") (pintype "passive"))
      (node (ref "C80") (pin "1") (pinfunction "1_1") (pintype "passive"))
      (node (ref "C81") (pin "1") (pinfunction "1_1") (pintype "passive"))
      (node (ref "C82") (pin "1") (pinfunction "1_1") (pintype "passive"))
      (node (ref "C85") (pin "1") (pinfunction "1_1") (pintype "passive"))
      (node (ref "C86") (pin "1") (pinfunction "1_1") (pintype "passive"))
      (node (ref "D1") (pin "2") (pinfunction "A_2") (pintype "passive"))
      (node (ref "D2") (pin "2") (pinfunction "A_2") (pintype "passive"))
      (node (ref "D3") (pin "2") (pinfunction "A_2") (pintype "passive"))
      (node (ref "D4") (pin "2") (pinfunction "A_2") (pintype "passive"))
      (node (ref "J4") (pin "20") (pinfunction "20_20") (pintype "passive"))
      (node (ref "J5") (pin "1") (pinfunction "1_1") (pintype "passive"))
      (node (ref "J5") (pin "2") (pinfunction "2_2") (pintype "passive"))
      (node (ref "J5") (pin "44") (pinfunction "44_44") (pintype "passive"))
      (node (ref "J5") (pin "45") (pinfunction "45_45") (pintype "passive"))
      (node (ref "LED4") (pin "3") (pinfunction "VSS_3") (pintype "power_in"))
      (node (ref "LED5") (pin "1") (pinfunction "K_1") (pintype "passive"))
      (node (ref "LED6") (pin "2") (pinfunction "K_2") (pintype "passive"))
      (node (ref "R37") (pin "1") (pinfunction "1_1") (pintype "passive"))
      (node (ref "R38") (pin "1") (pinfunction "1_1") (pintype "passive"))
      (node (ref "R50") (pin "1") (pinfunction "1_1") (pintype "passive"))
      (node (ref "R57") (pin "1") (pinfunction "1_1") (pintype "passive"))
      (node (ref "SW4") (pin "3") (pinfunction "C_3") (pintype "passive"))
      (node (ref "SW5") (pin "3") (pinfunction "C_3") (pintype "passive"))
      (node (ref "TP43") (pin "TP?") (pinfunction "Test_point_TP?") (pintype "passive"))
      (node (ref "U23") (pin "1") (pinfunction "GND_1") (pintype "power_in"))
      (node (ref "U23") (pin "2") (pinfunction "GND_2") (pintype "power_in"))
      (node (ref "U23") (pin "42") (pinfunction "GND_42") (pintype "power_in"))
      (node (ref "U23") (pin "43") (pinfunction "GND_43") (pintype "power_in"))
      (node (ref "U23") (pin "46") (pinfunction "GND_46") (pintype "power_in"))
      (node (ref "U23") (pin "47") (pinfunction "GND_47") (pintype "power_in"))
      (node (ref "U23") (pin "48") (pinfunction "GND_48") (pintype "power_in"))
      (node (ref "U23") (pin "49") (pinfunction "GND_49") (pintype "power_in"))
      (node (ref "U23") (pin "50") (pinfunction "GND_50") (pintype "power_in"))
      (node (ref "U23") (pin "51") (pinfunction "GND_51") (pintype "power_in"))
      (node (ref "U23") (pin "52") (pinfunction "GND_52") (pintype "power_in"))
      (node (ref "U23") (pin "53") (pinfunction "GND_53") (pintype "power_in"))
      (node (ref "U23") (pin "54") (pinfunction "GND_54") (pintype "power_in"))
      (node (ref "U23") (pin "55") (pinfunction "GND_55") (pintype "power_in"))
      (node (ref "U23") (pin "56") (pinfunction "GND_56") (pintype "power_in"))
      (node (ref "U23") (pin "57") (pinfunction "GND_57") (pintype "power_in"))
      (node (ref "U23") (pin "58") (pinfunction "GND_58") (pintype "power_in"))
      (node (ref "U23") (pin "59") (pinfunction "GND_59") (pintype "power_in"))
      (node (ref "U23") (pin "60") (pinfunction "GND_60") (pintype "power_in"))
      (node (ref "U23") (pin "61") (pinfunction "GND_61") (pintype "power_in"))
      (node (ref "U23") (pin "61_1") (pinfunction "GND_61_1") (pintype "power_in"))
      (node (ref "U23") (pin "61_2") (pinfunction "GND_61_2") (pintype "power_in"))
      (node (ref "U23") (pin "61_3") (pinfunction "GND_61_3") (pintype "power_in"))
      (node (ref "U23") (pin "61_4") (pinfunction "GND_61_4") (pintype "power_in"))
      (node (ref "U23") (pin "61_5") (pinfunction "GND_61_5") (pintype "power_in"))
      (node (ref "U23") (pin "61_6") (pinfunction "GND_61_6") (pintype "power_in"))
      (node (ref "U23") (pin "61_7") (pinfunction "GND_61_7") (pintype "power_in"))
      (node (ref "U23") (pin "61_8") (pinfunction "GND_61_8") (pintype "power_in"))
      (node (ref "U23") (pin "62") (pinfunction "GND_62") (pintype "power_in"))
      (node (ref "U23") (pin "63") (pinfunction "GND_63") (pintype "power_in"))
      (node (ref "U23") (pin "64") (pinfunction "GND_64") (pintype "power_in"))
      (node (ref "U23") (pin "65") (pinfunction "GND_65") (pintype "power_in"))
      (node (ref "U24") (pin "D2") (pinfunction "GND_D2") (pintype "power_in"))
      (node (ref "U25") (pin "4") (pinfunction "GND_4") (pintype "power_in"))
      (node (ref "U26") (pin "16") (pinfunction "ADDR_16") (pintype "input"))
      (node (ref "U26") (pin "17") (pinfunction "EP_17") (pintype "passive"))
      (node (ref "U26") (pin "6") (pinfunction "GND_6") (pintype "power_in"))
      (node (ref "U27") (pin "17") (pinfunction "EP_17") (pintype "passive"))
      (node (ref "U27") (pin "6") (pinfunction "GND_6") (pintype "power_in"))
      (node (ref "U28") (pin "A5") (pinfunction "GND_A5") (pintype "power_in"))
      (node (ref "U28") (pin "B2") (pinfunction "GND_B2") (pintype "power_in"))
      (node (ref "U28") (pin "E1") (pinfunction "GND_E1") (pintype "power_in"))
      (node (ref "U29") (pin "A5") (pinfunction "GND_A5") (pintype "power_in"))
      (node (ref "U29") (pin "B2") (pinfunction "GND_B2") (pintype "power_in"))
      (node (ref "U29") (pin "E1") (pinfunction "GND_E1") (pintype "power_in"))
      (node (ref "U30") (pin "A5") (pinfunction "GND_A5") (pintype "power_in"))
      (node (ref "U30") (pin "B2") (pinfunction "GND_B2") (pintype "power_in"))
      (node (ref "U30") (pin "E1") (pinfunction "GND_E1") (pintype "power_in"))
      (node (ref "U31") (pin "A5") (pinfunction "GND_A5") (pintype "power_in"))
      (node (ref "U31") (pin "B2") (pinfunction "GND_B2") (pintype "power_in"))
      (node (ref "U31") (pin "E1") (pinfunction "GND_E1") (pintype "power_in"))
      (node (ref "X1") (pin "2") (pinfunction "GND_2") (pintype "passive"))
    )
    (net (code "77") (name "Net-(D1-K)") (class "Default")
      (node (ref "C67") (pin "1") (pinfunction "1_1") (pintype "passive"))
      (node (ref "C74") (pin "2") (pinfunction "2_2") (pintype "passive"))
      (node (ref "D1") (pin "1") (pinfunction "K_1") (pintype "passive"))
      (node (ref "R65") (pin "1") (pinfunction "1_1") (pintype "passive"))
      (node (ref "TP32") (pin "TP?") (pinfunction "Test_point_TP?") (pintype "passive"))
      (node (ref "U29") (pin "A1") (pinfunction "VDD_A1") (pintype "power_in"))
      (node (ref "U29") (pin "B3") (pinfunction "RP_B3") (pintype "input"))
    )
    (net (code "78") (name "Net-(D2-K)") (class "Default")
      (node (ref "C68") (pin "1") (pinfunction "1_1") (pintype "passive"))
      (node (ref "C73") (pin "2") (pinfunction "2_2") (pintype "passive"))
      (node (ref "D2") (pin "1") (pinfunction "K_1") (pintype "passive"))
      (node (ref "R64") (pin "1") (pinfunction "1_1") (pintype "passive"))
      (node (ref "TP33") (pin "TP?") (pinfunction "Test_point_TP?") (pintype "passive"))
      (node (ref "U28") (pin "A1") (pinfunction "VDD_A1") (pintype "power_in"))
      (node (ref "U28") (pin "B3") (pinfunction "RP_B3") (pintype "input"))
    )
    (net (code "79") (name "Net-(D3-K)") (class "Default")
      (node (ref "C77") (pin "1") (pinfunction "1_1") (pintype "passive"))
      (node (ref "C83") (pin "2") (pinfunction "2_2") (pintype "passive"))
      (node (ref "D3") (pin "1") (pinfunction "K_1") (pintype "passive"))
      (node (ref "R68") (pin "1") (pinfunction "1_1") (pintype "passive"))
      (node (ref "TP36") (pin "TP?") (pinfunction "Test_point_TP?") (pintype "passive"))
      (node (ref "U30") (pin "A1") (pinfunction "VDD_A1") (pintype "power_in"))
      (node (ref "U30") (pin "B3") (pinfunction "RP_B3") (pintype "input"))
    )
    (net (code "80") (name "Net-(D4-K)") (class "Default")
      (node (ref "C78") (pin "1") (pinfunction "1_1") (pintype "passive"))
      (node (ref "C84") (pin "2") (pinfunction "2_2") (pintype "passive"))
      (node (ref "D4") (pin "1") (pinfunction "K_1") (pintype "passive"))
      (node (ref "R69") (pin "1") (pinfunction "1_1") (pintype "passive"))
      (node (ref "TP37") (pin "TP?") (pinfunction "Test_point_TP?") (pintype "passive"))
      (node (ref "U31") (pin "A1") (pinfunction "VDD_A1") (pintype "power_in"))
      (node (ref "U31") (pin "B3") (pinfunction "RP_B3") (pintype "input"))
    )
    (net (code "81") (name "Net-(L4-Pad2)") (class "Default")
      (node (ref "L4") (pin "2") (pinfunction "2_2") (pintype "passive"))
      (node (ref "U28") (pin "E2") (pinfunction "SW_E2") (pintype "power_in"))
      (node (ref "U28") (pin "E3") (pinfunction "SW_E3") (pintype "power_in"))
    )
    (net (code "82") (name "Net-(L5-Pad2)") (class "Default")
      (node (ref "L5") (pin "2") (pinfunction "2_2") (pintype "passive"))
      (node (ref "U29") (pin "E2") (pinfunction "SW_E2") (pintype "power_in"))
      (node (ref "U29") (pin "E3") (pinfunction "SW_E3") (pintype "power_in"))
    )
    (net (code "83") (name "Net-(L6-Pad2)") (class "Default")
      (node (ref "L6") (pin "2") (pinfunction "2_2") (pintype "passive"))
      (node (ref "U30") (pin "E2") (pinfunction "SW_E2") (pintype "power_in"))
      (node (ref "U30") (pin "E3") (pinfunction "SW_E3") (pintype "power_in"))
    )
    (net (code "84") (name "Net-(L7-Pad2)") (class "Default")
      (node (ref "L7") (pin "2") (pinfunction "2_2") (pintype "passive"))
      (node (ref "U31") (pin "E2") (pinfunction "SW_E2") (pintype "power_in"))
      (node (ref "U31") (pin "E3") (pinfunction "SW_E3") (pintype "power_in"))
    )
    (net (code "85") (name "Net-(LED5-A)") (class "Default")
      (node (ref "LED5") (pin "2") (pinfunction "A_2") (pintype "passive"))
      (node (ref "R34") (pin "2") (pinfunction "2_2") (pintype "passive"))
    )
    (net (code "86") (name "Net-(LED6-A)") (class "Default")
      (node (ref "LED6") (pin "1") (pinfunction "A_1") (pintype "passive"))
      (node (ref "R35") (pin "2") (pinfunction "2_2") (pintype "passive"))
    )
    (net (code "87") (name "Net-(SW4-B)") (class "Default")
      (node (ref "C50") (pin "1") (pinfunction "1_1") (pintype "passive"))
      (node (ref "R40") (pin "1") (pinfunction "1_1") (pintype "passive"))
      (node (ref "SW4") (pin "2") (pinfunction "B_2") (pintype "passive"))
    )
    (net (code "88") (name "Net-(U23-IO12)") (class "Default")
      (node (ref "R41") (pin "2") (pinfunction "2_2") (pintype "passive"))
      (node (ref "U23") (pin "16") (pinfunction "IO12_16") (pintype "bidirectional"))
    )
    (net (code "89") (name "Net-(U23-IO13)") (class "Default")
      (node (ref "R36") (pin "2") (pinfunction "2_2") (pintype "passive"))
      (node (ref "U23") (pin "17") (pinfunction "IO13_17") (pintype "bidirectional"))
    )
    (net (code "90") (name "Net-(U23-IO15)") (class "Default")
      (node (ref "C52") (pin "2") (pinfunction "2_2") (pintype "passive"))
      (node (ref "U23") (pin "19") (pinfunction "IO15_19") (pintype "bidirectional"))
    )
    (net (code "91") (name "Net-(U23-IO41)") (class "Default")
      (node (ref "R46") (pin "1") (pinfunction "1_1") (pintype "passive"))
      (node (ref "U23") (pin "37") (pinfunction "IO41_37") (pintype "bidirectional"))
    )
    (net (code "92") (name "Net-(U23-IO42)") (class "Default")
      (node (ref "R47") (pin "1") (pinfunction "1_1") (pintype "passive"))
      (node (ref "U23") (pin "38") (pinfunction "IO42_38") (pintype "bidirectional"))
    )
    (net (code "93") (name "Net-(U27-~{INT})") (class "Default")
      (node (ref "R49") (pin "1") (pinfunction "1_1") (pintype "passive"))
      (node (ref "U27") (pin "11") (pinfunction "~{INT}_11") (pintype "open_collector"))
    )
    (net (code "94") (name "Net-(U28-HV)") (class "Default")
      (node (ref "C73") (pin "1") (pinfunction "1_1") (pintype "passive"))
      (node (ref "U28") (pin "D1") (pinfunction "HV_D1") (pintype "power_in"))
    )
    (net (code "95") (name "Net-(U28-PUMP)") (class "Default")
      (node (ref "C75") (pin "2") (pinfunction "2_2") (pintype "passive"))
      (node (ref "U28") (pin "A4") (pinfunction "PUMP_A4") (pintype "power_in"))
    )
    (net (code "96") (name "Net-(U28-REG)") (class "Default")
      (node (ref "C69") (pin "2") (pinfunction "2_2") (pintype "passive"))
      (node (ref "U28") (pin "B5") (pinfunction "REG_B5") (pintype "power_in"))
    )
    (net (code "97") (name "Net-(U28-RM)") (class "Default")
      (node (ref "L4") (pin "1") (pinfunction "1_1") (pintype "passive"))
      (node (ref "R64") (pin "2") (pinfunction "2_2") (pintype "passive"))
      (node (ref "U28") (pin "B4") (pinfunction "RM_B4") (pintype "input"))
    )
    (net (code "98") (name "Net-(U28-SDO)") (class "Default")
      (node (ref "R62") (pin "2") (pinfunction "2_2") (pintype "passive"))
      (node (ref "U28") (pin "C5") (pinfunction "SDO_C5") (pintype "output"))
    )
    (net (code "99") (name "Net-(U29-HV)") (class "Default")
      (node (ref "C74") (pin "1") (pinfunction "1_1") (pintype "passive"))
      (node (ref "U29") (pin "D1") (pinfunction "HV_D1") (pintype "power_in"))
    )
    (net (code "100") (name "Net-(U29-PUMP)") (class "Default")
      (node (ref "C76") (pin "2") (pinfunction "2_2") (pintype "passive"))
      (node (ref "U29") (pin "A4") (pinfunction "PUMP_A4") (pintype "power_in"))
    )
    (net (code "101") (name "Net-(U29-REG)") (class "Default")
      (node (ref "C70") (pin "2") (pinfunction "2_2") (pintype "passive"))
      (node (ref "U29") (pin "B5") (pinfunction "REG_B5") (pintype "power_in"))
    )
    (net (code "102") (name "Net-(U29-RM)") (class "Default")
      (node (ref "L5") (pin "1") (pinfunction "1_1") (pintype "passive"))
      (node (ref "R65") (pin "2") (pinfunction "2_2") (pintype "passive"))
      (node (ref "U29") (pin "B4") (pinfunction "RM_B4") (pintype "input"))
    )
    (net (code "103") (name "Net-(U29-SDO)") (class "Default")
      (node (ref "R63") (pin "2") (pinfunction "2_2") (pintype "passive"))
      (node (ref "U29") (pin "C5") (pinfunction "SDO_C5") (pintype "output"))
    )
    (net (code "104") (name "Net-(U30-HV)") (class "Default")
      (node (ref "C83") (pin "1") (pinfunction "1_1") (pintype "passive"))
      (node (ref "U30") (pin "D1") (pinfunction "HV_D1") (pintype "power_in"))
    )
    (net (code "105") (name "Net-(U30-PUMP)") (class "Default")
      (node (ref "C85") (pin "2") (pinfunction "2_2") (pintype "passive"))
      (node (ref "U30") (pin "A4") (pinfunction "PUMP_A4") (pintype "power_in"))
    )
    (net (code "106") (name "Net-(U30-REG)") (class "Default")
      (node (ref "C79") (pin "2") (pinfunction "2_2") (pintype "passive"))
      (node (ref "U30") (pin "B5") (pinfunction "REG_B5") (pintype "power_in"))
    )
    (net (code "107") (name "Net-(U30-RM)") (class "Default")
      (node (ref "L6") (pin "1") (pinfunction "1_1") (pintype "passive"))
      (node (ref "R68") (pin "2") (pinfunction "2_2") (pintype "passive"))
      (node (ref "U30") (pin "B4") (pinfunction "RM_B4") (pintype "input"))
    )
    (net (code "108") (name "Net-(U30-SDO)") (class "Default")
      (node (ref "R66") (pin "2") (pinfunction "2_2") (pintype "passive"))
      (node (ref "U30") (pin "C5") (pinfunction "SDO_C5") (pintype "output"))
    )
    (net (code "109") (name "Net-(U31-HV)") (class "Default")
      (node (ref "C84") (pin "1") (pinfunction "1_1") (pintype "passive"))
      (node (ref "U31") (pin "D1") (pinfunction "HV_D1") (pintype "power_in"))
    )
    (net (code "110") (name "Net-(U31-PUMP)") (class "Default")
      (node (ref "C86") (pin "2") (pinfunction "2_2") (pintype "passive"))
      (node (ref "U31") (pin "A4") (pinfunction "PUMP_A4") (pintype "power_in"))
    )
    (net (code "111") (name "Net-(U31-REG)") (class "Default")
      (node (ref "C80") (pin "2") (pinfunction "2_2") (pintype "passive"))
      (node (ref "U31") (pin "B5") (pinfunction "REG_B5") (pintype "power_in"))
    )
    (net (code "112") (name "Net-(U31-RM)") (class "Default")
      (node (ref "L7") (pin "1") (pinfunction "1_1") (pintype "passive"))
      (node (ref "R69") (pin "2") (pinfunction "2_2") (pintype "passive"))
      (node (ref "U31") (pin "B4") (pinfunction "RM_B4") (pintype "input"))
    )
    (net (code "113") (name "Net-(U31-SDO)") (class "Default")
      (node (ref "R67") (pin "2") (pinfunction "2_2") (pintype "passive"))
      (node (ref "U31") (pin "C5") (pinfunction "SDO_C5") (pintype "output"))
    )
    (net (code "114") (name "Net-(X1-OUT)") (class "Default")
      (node (ref "C52") (pin "1") (pinfunction "1_1") (pintype "passive"))
      (node (ref "X1") (pin "3") (pinfunction "OUT_3") (pintype "passive"))
    )
    (net (code "115") (name "unconnected-(J3-PadP1)") (class "Default")
      (node (ref "J3") (pin "P1") (pinfunction "P1_P1") (pintype "passive+no_connect"))
    )
    (net (code "116") (name "unconnected-(J3-PadP2)") (class "Default")
      (node (ref "J3") (pin "P2") (pinfunction "P2_P2") (pintype "passive+no_connect"))
    )
    (net (code "117") (name "unconnected-(J5-Pad46)") (class "Default")
      (node (ref "J5") (pin "46") (pinfunction "46_46") (pintype "passive+no_connect"))
    )
    (net (code "118") (name "unconnected-(J5-Pad47)") (class "Default")
      (node (ref "J5") (pin "47") (pinfunction "47_47") (pintype "passive+no_connect"))
    )
    (net (code "119") (name "unconnected-(LED4-DOUT-Pad2)") (class "Default")
      (node (ref "LED4") (pin "2") (pinfunction "DOUT_2") (pintype "output+no_connect"))
    )
    (net (code "120") (name "unconnected-(SW4-A-Pad1)") (class "Default")
      (node (ref "SW4") (pin "1") (pinfunction "A_1") (pintype "passive+no_connect"))
    )
    (net (code "121") (name "unconnected-(SW4-D-Pad4)") (class "Default")
      (node (ref "SW4") (pin "4") (pinfunction "D_4") (pintype "passive+no_connect"))
    )
    (net (code "122") (name "unconnected-(SW5-A-Pad1)") (class "Default")
      (node (ref "SW5") (pin "1") (pinfunction "A_1") (pintype "passive+no_connect"))
    )
    (net (code "123") (name "unconnected-(SW5-D-Pad4)") (class "Default")
      (node (ref "SW5") (pin "4") (pinfunction "D_4") (pintype "passive+no_connect"))
    )
    (net (code "124") (name "unconnected-(U23-IO16-Pad20)") (class "Default")
      (node (ref "U23") (pin "20") (pinfunction "IO16_20") (pintype "bidirectional+no_connect"))
    )
    (net (code "125") (name "unconnected-(U28-TST0-PadC2)") (class "Default")
      (node (ref "U28") (pin "C2") (pinfunction "TST0_C2") (pintype "passive+no_connect"))
    )
    (net (code "126") (name "unconnected-(U28-TST4-PadC3)") (class "Default")
      (node (ref "U28") (pin "C3") (pinfunction "TST4_C3") (pintype "passive+no_connect"))
    )
    (net (code "127") (name "unconnected-(U28-TST5-PadA3)") (class "Default")
      (node (ref "U28") (pin "A3") (pinfunction "TST5_A3") (pintype "passive+no_connect"))
    )
    (net (code "128") (name "unconnected-(U29-TST0-PadC2)") (class "Default")
      (node (ref "U29") (pin "C2") (pinfunction "TST0_C2") (pintype "passive+no_connect"))
    )
    (net (code "129") (name "unconnected-(U29-TST4-PadC3)") (class "Default")
      (node (ref "U29") (pin "C3") (pinfunction "TST4_C3") (pintype "passive+no_connect"))
    )
    (net (code "130") (name "unconnected-(U29-TST5-PadA3)") (class "Default")
      (node (ref "U29") (pin "A3") (pinfunction "TST5_A3") (pintype "passive+no_connect"))
    )
    (net (code "131") (name "unconnected-(U30-TST0-PadC2)") (class "Default")
      (node (ref "U30") (pin "C2") (pinfunction "TST0_C2") (pintype "passive+no_connect"))
    )
    (net (code "132") (name "unconnected-(U30-TST4-PadC3)") (class "Default")
      (node (ref "U30") (pin "C3") (pinfunction "TST4_C3") (pintype "passive+no_connect"))
    )
    (net (code "133") (name "unconnected-(U30-TST5-PadA3)") (class "Default")
      (node (ref "U30") (pin "A3") (pinfunction "TST5_A3") (pintype "passive+no_connect"))
    )
    (net (code "134") (name "unconnected-(U31-TST0-PadC2)") (class "Default")
      (node (ref "U31") (pin "C2") (pinfunction "TST0_C2") (pintype "passive+no_connect"))
    )
    (net (code "135") (name "unconnected-(U31-TST4-PadC3)") (class "Default")
      (node (ref "U31") (pin "C3") (pinfunction "TST4_C3") (pintype "passive+no_connect"))
    )
    (net (code "136") (name "unconnected-(U31-TST5-PadA3)") (class "Default")
      (node (ref "U31") (pin "A3") (pinfunction "TST5_A3") (pintype "passive+no_connect"))
    )
    (net (code "137") (name "unconnected-(X1-Enable{slash}Disable-Pad1)") (class "Default")
      (node (ref "X1") (pin "1") (pinfunction "Enable/Disable_1") (pintype "passive+no_connect"))
    )
  )
)
